# 2014_FDP_ACTIONNEUR.net
KiCad netlist of a schematic drawn in Altium Designer
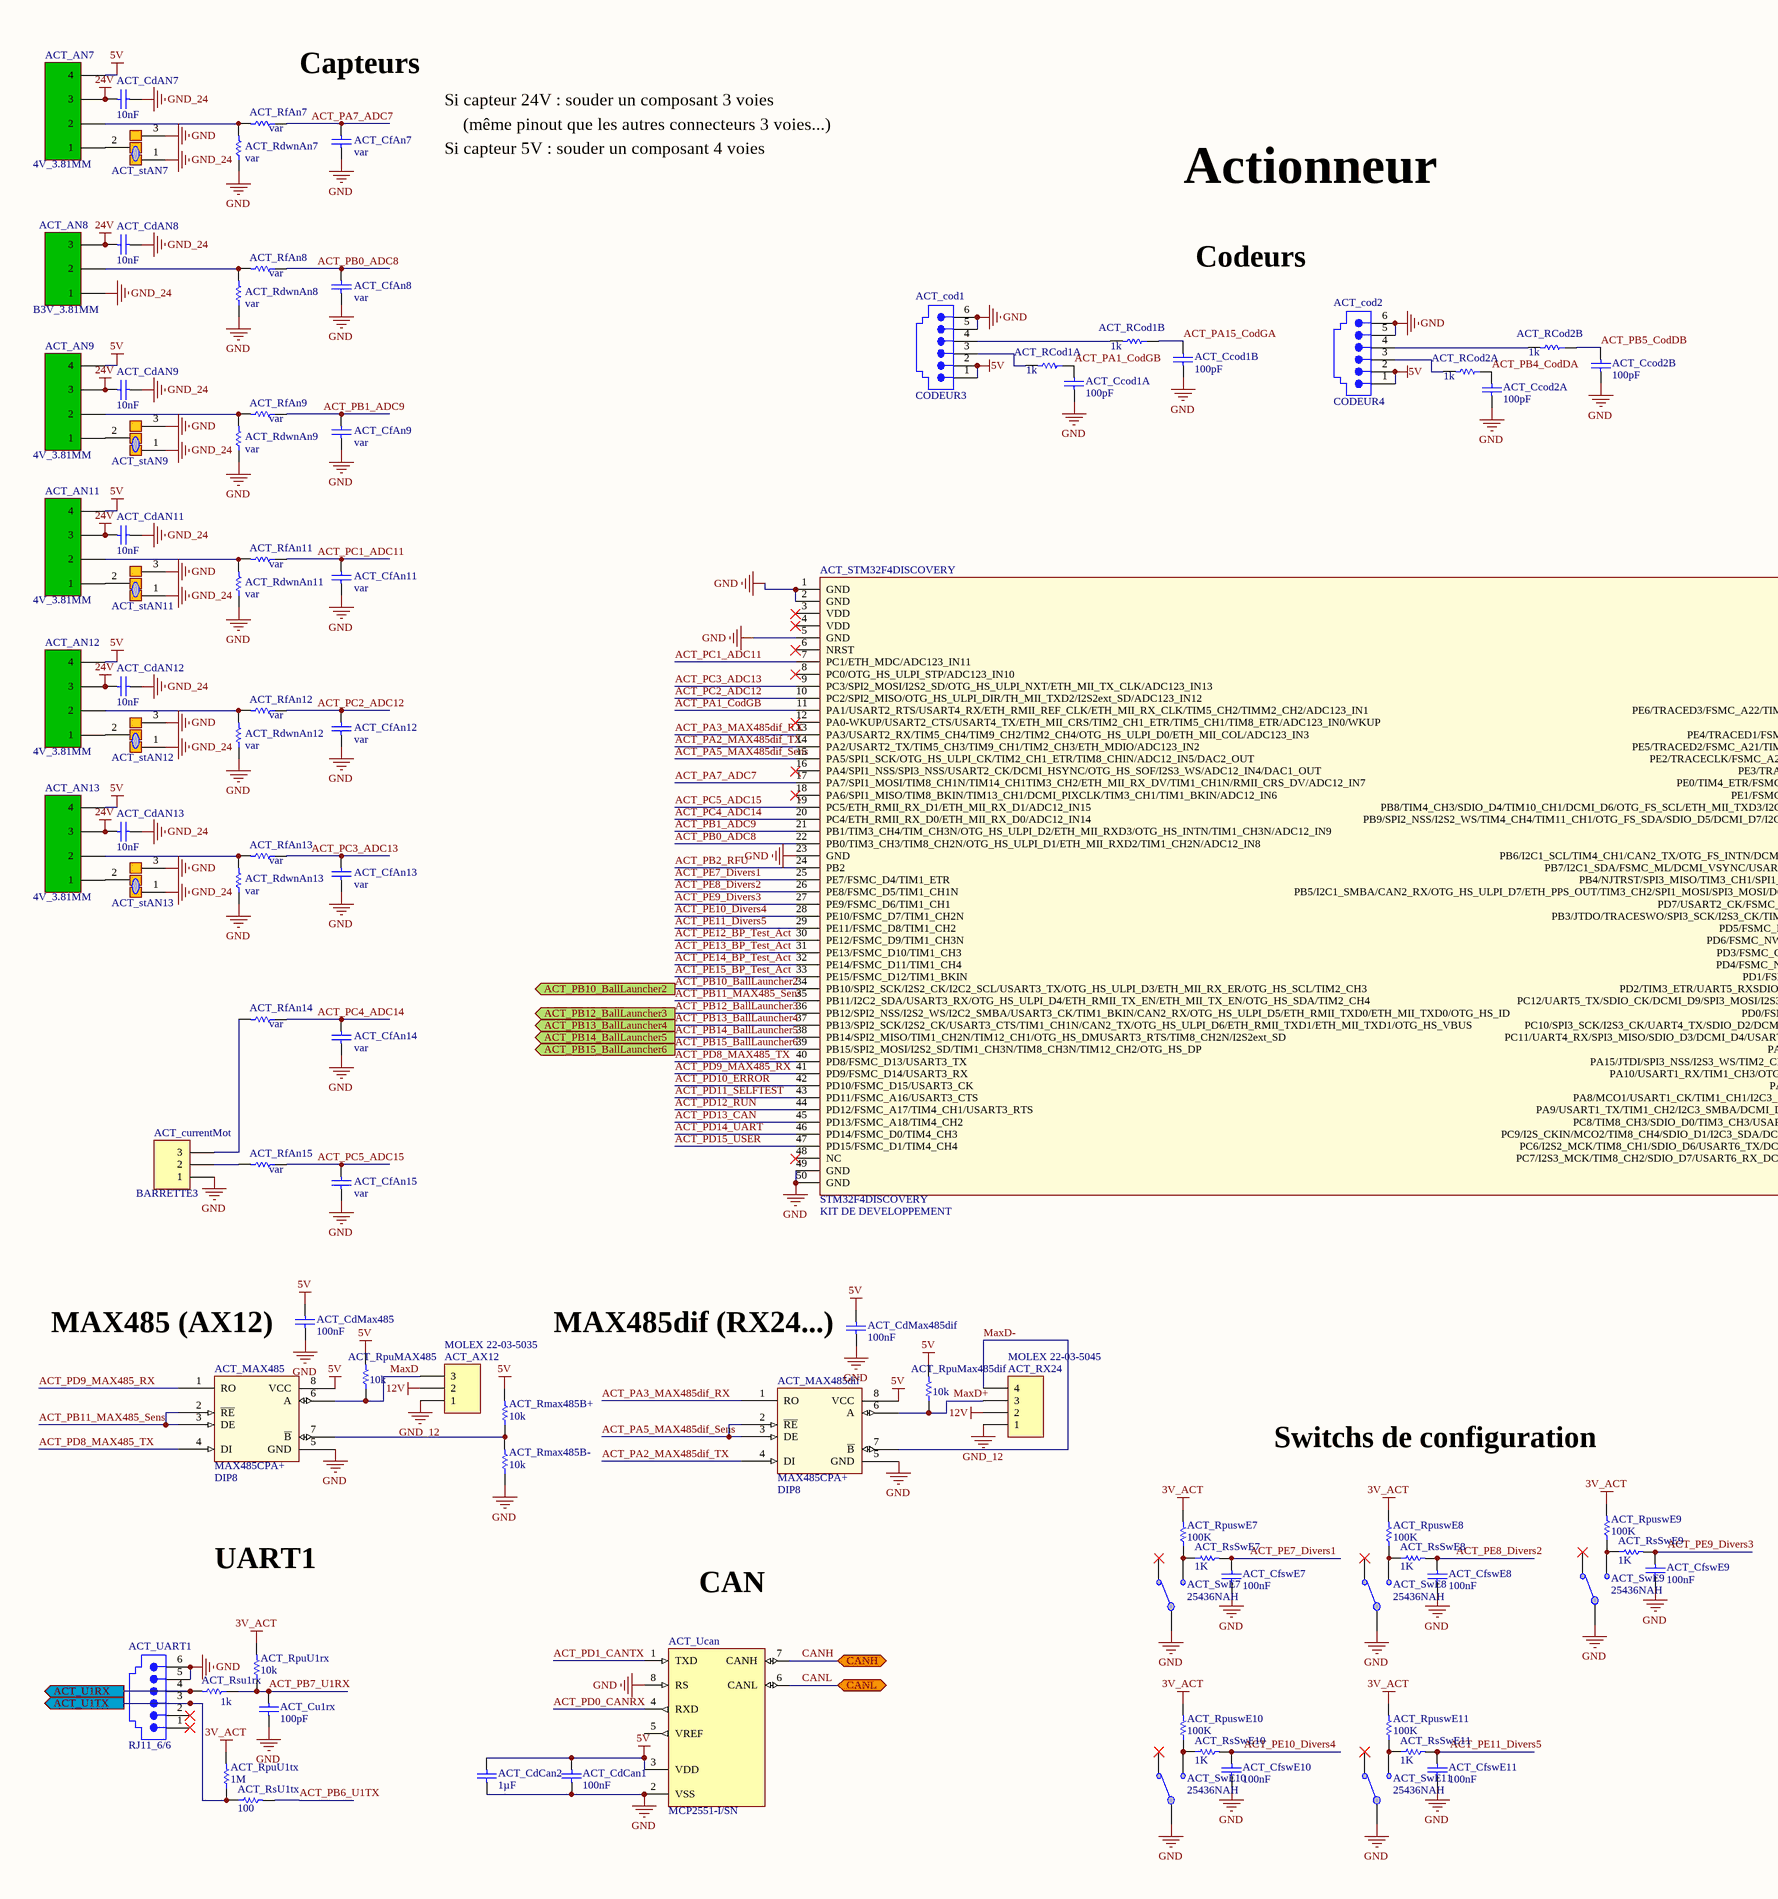
[diagram p0: 2014_FDP_ACTIONNEUR.SchDoc, left]
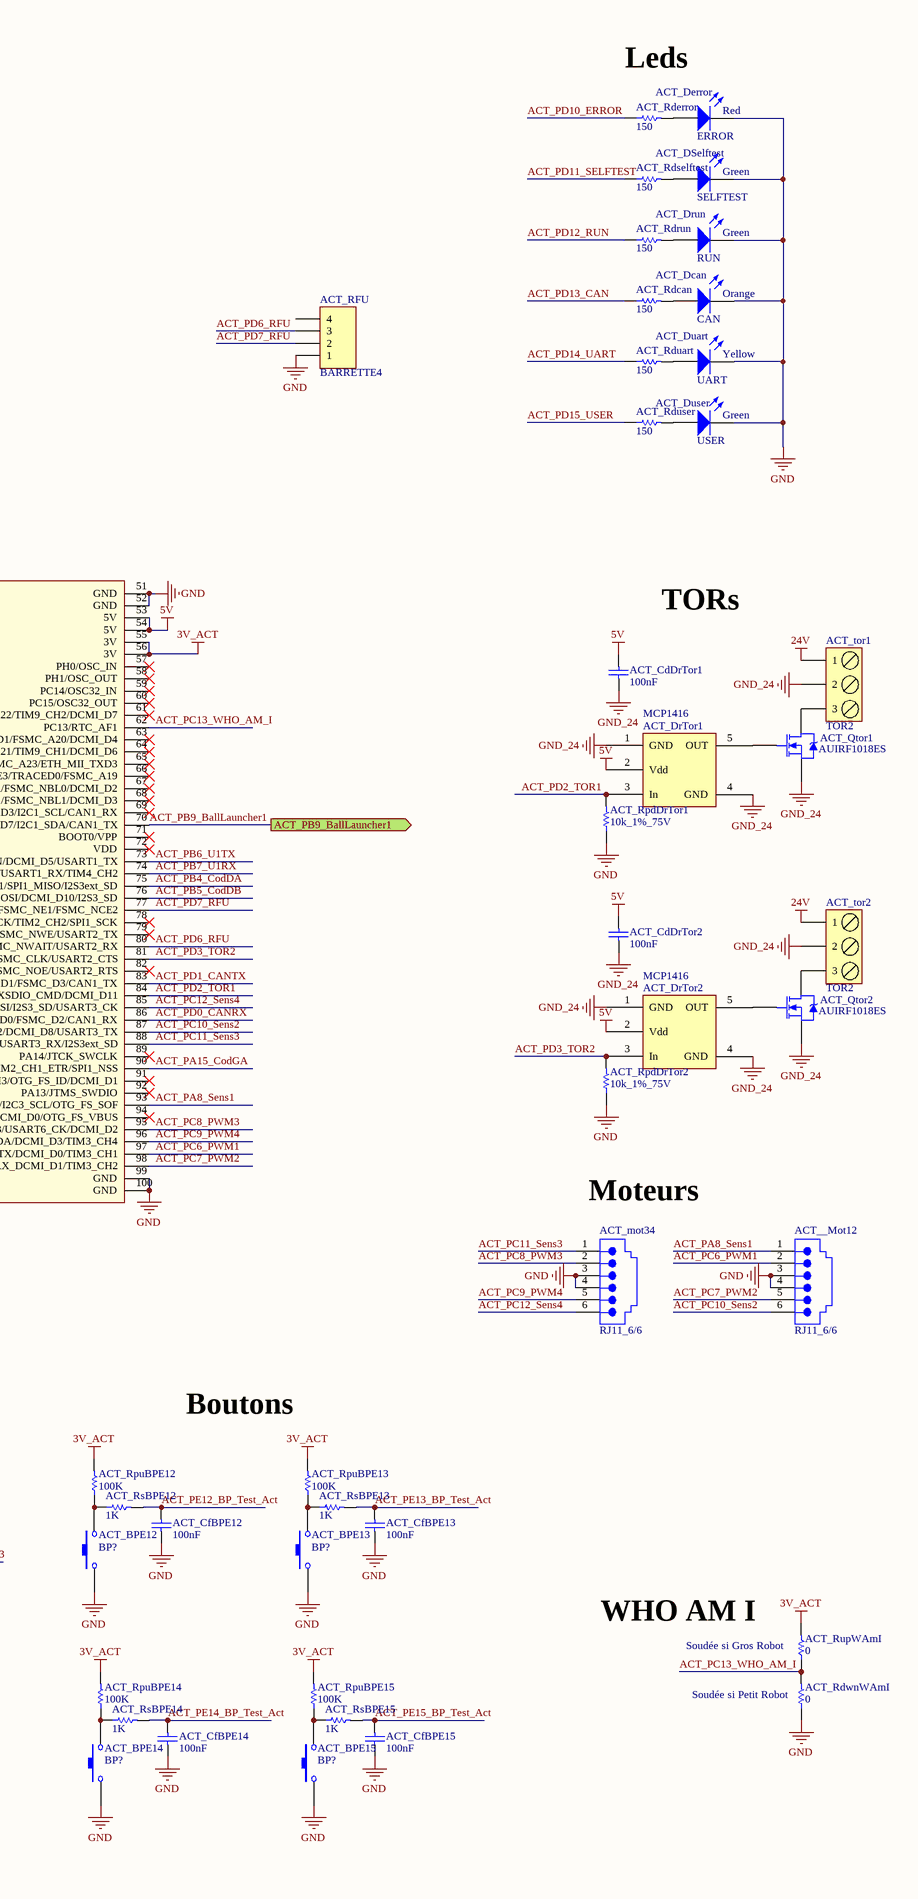
[diagram p1: 2014_FDP_ACTIONNEUR.SchDoc, right]

(export (version "E")
  (design (tool "Eeschema 10.0.6"))
  (components
    (comp (ref "ACT_AN7")
      (value "4V_3.81MM")
      (footprint "BORNIER_4V_3.81MM")
      (libsource (lib "Connecteur") (part "BORNIER_4V_3.81MM"))
    )
    (comp (ref "ACT_AN8")
      (value "B3V_3.81MM")
      (footprint "BORNIER_3V_3.81MM")
      (libsource (lib "Connecteur") (part "BORNIER_3V_3.81MM"))
    )
    (comp (ref "ACT_AN9")
      (value "4V_3.81MM")
      (footprint "BORNIER_4V_3.81MM")
      (libsource (lib "Connecteur") (part "BORNIER_4V_3.81MM"))
    )
    (comp (ref "ACT_AN11")
      (value "4V_3.81MM")
      (footprint "BORNIER_4V_3.81MM")
      (libsource (lib "Connecteur") (part "BORNIER_4V_3.81MM"))
    )
    (comp (ref "ACT_AN12")
      (value "4V_3.81MM")
      (footprint "BORNIER_4V_3.81MM")
      (libsource (lib "Connecteur") (part "BORNIER_4V_3.81MM"))
    )
    (comp (ref "ACT_AN13")
      (value "4V_3.81MM")
      (footprint "BORNIER_4V_3.81MM")
      (libsource (lib "Connecteur") (part "BORNIER_4V_3.81MM"))
    )
    (comp (ref "ACT_AX12")
      (value "MOLEX 22-03-5035")
      (footprint "MOLEX3_2.5MM")
      (description "Header, 3-Pin")
      (fields (field (name "PUBLISHER") "Altium Limited"))
      (libsource (lib "Connecteur") (part "BARRETTE3"))
    )
    (comp (ref "ACT_BPE12")
      (value "BP?")
      (footprint "Switch 6x6 Vertical")
      (description "Switch tactil 6mm x 6mm Vertical")
      (fields (field (name "PUBLISHER") "Damien Guitton"))
      (libsource (lib "_ROBOT") (part "SW_Pushbutton_6x6mm_Vertical"))
    )
    (comp (ref "ACT_BPE13")
      (value "BP?")
      (footprint "Switch 6x6 Vertical")
      (description "Switch tactil 6mm x 6mm Vertical")
      (fields (field (name "PUBLISHER") "Damien Guitton"))
      (libsource (lib "_ROBOT") (part "SW_Pushbutton_6x6mm_Vertical"))
    )
    (comp (ref "ACT_BPE14")
      (value "BP?")
      (footprint "Switch 6x6 Vertical")
      (description "Switch tactil 6mm x 6mm Vertical")
      (fields (field (name "PUBLISHER") "Damien Guitton"))
      (libsource (lib "_ROBOT") (part "SW_Pushbutton_6x6mm_Vertical"))
    )
    (comp (ref "ACT_BPE15")
      (value "BP?")
      (footprint "Switch 6x6 Vertical")
      (description "Switch tactil 6mm x 6mm Vertical")
      (fields (field (name "PUBLISHER") "Damien Guitton"))
      (libsource (lib "_ROBOT") (part "SW_Pushbutton_6x6mm_Vertical"))
    )
    (comp (ref "ACT_Ccod1A")
      (value "100pF")
      (footprint "C0805_N")
      (description "Capacitor")
      (fields (field (name "PUBLISHER") "Altium Limited"))
      (libsource (lib "_ROBOT") (part "Condensateur"))
    )
    (comp (ref "ACT_Ccod1B")
      (value "100pF")
      (footprint "C0805_N")
      (description "Capacitor")
      (fields (field (name "PUBLISHER") "Altium Limited"))
      (libsource (lib "_ROBOT") (part "Condensateur"))
    )
    (comp (ref "ACT_Ccod2A")
      (value "100pF")
      (footprint "C0805_N")
      (description "Capacitor")
      (fields (field (name "PUBLISHER") "Altium Limited"))
      (libsource (lib "_ROBOT") (part "Condensateur"))
    )
    (comp (ref "ACT_Ccod2B")
      (value "100pF")
      (footprint "C0805_N")
      (description "Capacitor")
      (fields (field (name "PUBLISHER") "Altium Limited"))
      (libsource (lib "_ROBOT") (part "Condensateur"))
    )
    (comp (ref "ACT_CdAN7")
      (value "10nF")
      (footprint "C0805_N")
      (description "Capacitor")
      (fields (field (name "PUBLISHER") "Altium Limited"))
      (libsource (lib "_ROBOT") (part "Condensateur"))
    )
    (comp (ref "ACT_CdAN8")
      (value "10nF")
      (footprint "C0805_N")
      (description "Capacitor")
      (fields (field (name "PUBLISHER") "Altium Limited"))
      (libsource (lib "_ROBOT") (part "Condensateur"))
    )
    (comp (ref "ACT_CdAN9")
      (value "10nF")
      (footprint "C0805_N")
      (description "Capacitor")
      (fields (field (name "PUBLISHER") "Altium Limited"))
      (libsource (lib "_ROBOT") (part "Condensateur"))
    )
    (comp (ref "ACT_CdAN11")
      (value "10nF")
      (footprint "C0805_N")
      (description "Capacitor")
      (fields (field (name "PUBLISHER") "Altium Limited"))
      (libsource (lib "_ROBOT") (part "Condensateur"))
    )
    (comp (ref "ACT_CdAN12")
      (value "10nF")
      (footprint "C0805_N")
      (description "Capacitor")
      (fields (field (name "PUBLISHER") "Altium Limited"))
      (libsource (lib "_ROBOT") (part "Condensateur"))
    )
    (comp (ref "ACT_CdAN13")
      (value "10nF")
      (footprint "C0805_N")
      (description "Capacitor")
      (fields (field (name "PUBLISHER") "Altium Limited"))
      (libsource (lib "_ROBOT") (part "Condensateur"))
    )
    (comp (ref "ACT_CdCan1")
      (value "100nF")
      (footprint "C0805_N")
      (description "Capacitor")
      (fields (field (name "PUBLISHER") "Altium Limited"))
      (libsource (lib "_ROBOT") (part "Condensateur"))
    )
    (comp (ref "ACT_CdCan2")
      (value "1µF")
      (footprint "C0805_N")
      (description "Capacitor")
      (fields (field (name "PUBLISHER") "Altium Limited"))
      (libsource (lib "_ROBOT") (part "Condensateur"))
    )
    (comp (ref "ACT_CdDrTor1")
      (value "100nF")
      (footprint "C0805_N")
      (description "Capacitor")
      (fields (field (name "PUBLISHER") "Altium Limited"))
      (libsource (lib "DG_Condensateur") (part "Capacitor"))
    )
    (comp (ref "ACT_CdDrTor2")
      (value "100nF")
      (footprint "C0805_N")
      (description "Capacitor")
      (fields (field (name "PUBLISHER") "Altium Limited"))
      (libsource (lib "DG_Condensateur") (part "Capacitor"))
    )
    (comp (ref "ACT_CdMax485")
      (value "100nF")
      (footprint "C0805_N")
      (description "Capacitor")
      (fields (field (name "PUBLISHER") "Altium Limited"))
      (libsource (lib "_ROBOT") (part "Condensateur"))
    )
    (comp (ref "ACT_CdMax485dif")
      (value "100nF")
      (footprint "C0805_N")
      (description "Capacitor")
      (fields (field (name "PUBLISHER") "Altium Limited"))
      (libsource (lib "_ROBOT") (part "Condensateur"))
    )
    (comp (ref "ACT_CfAn7")
      (value "var")
      (footprint "C0805_N")
      (description "Capacitor")
      (fields (field (name "PUBLISHER") "Altium Limited"))
      (libsource (lib "_ROBOT") (part "Condensateur"))
    )
    (comp (ref "ACT_CfAn8")
      (value "var")
      (footprint "C0805_N")
      (description "Capacitor")
      (fields (field (name "PUBLISHER") "Altium Limited"))
      (libsource (lib "_ROBOT") (part "Condensateur"))
    )
    (comp (ref "ACT_CfAn9")
      (value "var")
      (footprint "C0805_N")
      (description "Capacitor")
      (fields (field (name "PUBLISHER") "Altium Limited"))
      (libsource (lib "_ROBOT") (part "Condensateur"))
    )
    (comp (ref "ACT_CfAn11")
      (value "var")
      (footprint "C0805_N")
      (description "Capacitor")
      (fields (field (name "PUBLISHER") "Altium Limited"))
      (libsource (lib "_ROBOT") (part "Condensateur"))
    )
    (comp (ref "ACT_CfAn12")
      (value "var")
      (footprint "C0805_N")
      (description "Capacitor")
      (fields (field (name "PUBLISHER") "Altium Limited"))
      (libsource (lib "_ROBOT") (part "Condensateur"))
    )
    (comp (ref "ACT_CfAn13")
      (value "var")
      (footprint "C0805_N")
      (description "Capacitor")
      (fields (field (name "PUBLISHER") "Altium Limited"))
      (libsource (lib "_ROBOT") (part "Condensateur"))
    )
    (comp (ref "ACT_CfAn14")
      (value "var")
      (footprint "C0805_N")
      (description "Capacitor")
      (fields (field (name "PUBLISHER") "Altium Limited"))
      (libsource (lib "_ROBOT") (part "Condensateur"))
    )
    (comp (ref "ACT_CfAn15")
      (value "var")
      (footprint "C0805_N")
      (description "Capacitor")
      (fields (field (name "PUBLISHER") "Altium Limited"))
      (libsource (lib "_ROBOT") (part "Condensateur"))
    )
    (comp (ref "ACT_CfBPE12")
      (value "100nF")
      (footprint "C0805_N")
      (description "Capacitor")
      (fields (field (name "PUBLISHER") "Altium Limited"))
      (libsource (lib "_ROBOT") (part "Condensateur"))
    )
    (comp (ref "ACT_CfBPE13")
      (value "100nF")
      (footprint "C0805_N")
      (description "Capacitor")
      (fields (field (name "PUBLISHER") "Altium Limited"))
      (libsource (lib "_ROBOT") (part "Condensateur"))
    )
    (comp (ref "ACT_CfBPE14")
      (value "100nF")
      (footprint "C0805_N")
      (description "Capacitor")
      (fields (field (name "PUBLISHER") "Altium Limited"))
      (libsource (lib "_ROBOT") (part "Condensateur"))
    )
    (comp (ref "ACT_CfBPE15")
      (value "100nF")
      (footprint "C0805_N")
      (description "Capacitor")
      (fields (field (name "PUBLISHER") "Altium Limited"))
      (libsource (lib "_ROBOT") (part "Condensateur"))
    )
    (comp (ref "ACT_CfswE7")
      (value "100nF")
      (footprint "C0805_N")
      (description "Capacitor")
      (fields (field (name "PUBLISHER") "Altium Limited"))
      (libsource (lib "_ROBOT") (part "Condensateur"))
    )
    (comp (ref "ACT_CfswE8")
      (value "100nF")
      (footprint "C0805_N")
      (description "Capacitor")
      (fields (field (name "PUBLISHER") "Altium Limited"))
      (libsource (lib "_ROBOT") (part "Condensateur"))
    )
    (comp (ref "ACT_CfswE9")
      (value "100nF")
      (footprint "C0805_N")
      (description "Capacitor")
      (fields (field (name "PUBLISHER") "Altium Limited"))
      (libsource (lib "_ROBOT") (part "Condensateur"))
    )
    (comp (ref "ACT_CfswE10")
      (value "100nF")
      (footprint "C0805_N")
      (description "Capacitor")
      (fields (field (name "PUBLISHER") "Altium Limited"))
      (libsource (lib "_ROBOT") (part "Condensateur"))
    )
    (comp (ref "ACT_CfswE11")
      (value "100nF")
      (footprint "C0805_N")
      (description "Capacitor")
      (fields (field (name "PUBLISHER") "Altium Limited"))
      (libsource (lib "_ROBOT") (part "Condensateur"))
    )
    (comp (ref "ACT_cod1")
      (value "CODEUR3")
      (footprint "RJ11_6/6 - droit")
      (description "Right Angle, Standard Profile, Offset Latch DECconnect, Flangeless PCB Jack")
      (fields (field (name "PUBLISHER") "Altium Limited"))
      (libsource (lib "miniprojet") (part "RJ11_6/6"))
    )
    (comp (ref "ACT_cod2")
      (value "CODEUR4")
      (footprint "RJ11_6/6 - droit")
      (description "Right Angle, Standard Profile, Offset Latch DECconnect, Flangeless PCB Jack")
      (fields (field (name "PUBLISHER") "Altium Limited"))
      (libsource (lib "miniprojet") (part "RJ11_6/6"))
    )
    (comp (ref "ACT_Cu1rx")
      (value "100pF")
      (footprint "C0805_N")
      (description "Capacitor")
      (fields (field (name "PUBLISHER") "Altium Limited"))
      (libsource (lib "_ROBOT") (part "Condensateur"))
    )
    (comp (ref "ACT_currentMot")
      (value "BARRETTE3")
      (footprint "HE14_3")
      (description "Header, 3-Pin")
      (fields (field (name "PUBLISHER") "Altium Limited"))
      (libsource (lib "") (part "BARRETTE3_1"))
    )
    (comp (ref "ACT_Dcan")
      (value "CAN")
      (footprint "LED_0805")
      (description "Typical LED")
      (fields (field (name "PUBLISHER") "Altium Limited"))
      (libsource (lib "_ROBOT") (part "LED"))
    )
    (comp (ref "ACT_Derror")
      (value "ERROR")
      (footprint "LED_0805")
      (description "Typical LED")
      (fields (field (name "PUBLISHER") "Altium Limited"))
      (libsource (lib "_ROBOT") (part "LED"))
    )
    (comp (ref "ACT_DrTor1")
      (value "MCP1416")
      (footprint "SOT23-5AN")
      (libsource (lib "GAL") (part "MCP1402"))
    )
    (comp (ref "ACT_DrTor2")
      (value "MCP1416")
      (footprint "SOT23-5AN")
      (libsource (lib "GAL") (part "MCP1402"))
    )
    (comp (ref "ACT_Drun")
      (value "RUN")
      (footprint "LED_0805")
      (description "Typical LED")
      (fields (field (name "PUBLISHER") "Altium Limited"))
      (libsource (lib "_ROBOT") (part "LED"))
    )
    (comp (ref "ACT_DSelftest")
      (value "SELFTEST")
      (footprint "LED_0805")
      (description "Typical LED")
      (fields (field (name "PUBLISHER") "Altium Limited"))
      (libsource (lib "_ROBOT") (part "LED"))
    )
    (comp (ref "ACT_Duart")
      (value "UART")
      (footprint "LED_0805")
      (description "Typical LED")
      (fields (field (name "PUBLISHER") "Altium Limited"))
      (libsource (lib "_ROBOT") (part "LED"))
    )
    (comp (ref "ACT_Duser")
      (value "USER")
      (footprint "LED_0805")
      (description "Typical LED")
      (fields (field (name "PUBLISHER") "Altium Limited"))
      (libsource (lib "_ROBOT") (part "LED"))
    )
    (comp (ref "ACT_MAX485")
      (value "MAX485CPA+_DIP8")
      (footprint "SO8_N")
      (description "EMETTEUR/RECEPTEUR FAIBLE PUISSANCE DE LIAISONS RS422/RS485 - DIP8")
      (fields (field (name "TYPE") "MAX485CPA+") (field (name "PACKAGE") "DIP8"))
      (libsource (lib "circuits integres") (part "MAX485CPA+_DIP8"))
    )
    (comp (ref "ACT_MAX485dif")
      (value "MAX485CPA+_DIP8")
      (footprint "SO8_N")
      (description "EMETTEUR/RECEPTEUR FAIBLE PUISSANCE DE LIAISONS RS422/RS485 - DIP8")
      (fields (field (name "TYPE") "MAX485CPA+") (field (name "PACKAGE") "DIP8"))
      (libsource (lib "circuits integres") (part "MAX485CPA+_DIP8"))
    )
    (comp (ref "ACT_mot34")
      (value "RJ11_6/6")
      (footprint "RJ11_6/6")
      (description "Right Angle, Standard Profile, Offset Latch DECconnect, Flangeless PCB Jack")
      (fields (field (name "PUBLISHER") "Altium Limited"))
      (libsource (lib "Connecteur") (part "RJ11_6/6"))
    )
    (comp (ref "ACT_Qtor1")
      (value "AUIRF1018ES")
      (footprint "D2PAK")
      (description "HEXFET N-Channel Power MOSFET")
      (fields (field (name "PUBLISHER") "Altium Limited"))
      (libsource (lib "IR Discrete MOSFET - Power") (part "IRF1010S"))
    )
    (comp (ref "ACT_Qtor2")
      (value "AUIRF1018ES")
      (footprint "D2PAK")
      (description "HEXFET N-Channel Power MOSFET")
      (fields (field (name "PUBLISHER") "Altium Limited"))
      (libsource (lib "IR Discrete MOSFET - Power") (part "IRF1010S"))
    )
    (comp (ref "ACT_RCod1A")
      (value "1k")
      (footprint "R1206_N")
      (description "Resistor")
      (fields (field (name "PUBLISHER") "Altium Limited"))
      (libsource (lib "_ROBOT") (part "Resistor"))
    )
    (comp (ref "ACT_RCod1B")
      (value "1k")
      (footprint "R1206_N")
      (description "Resistor")
      (fields (field (name "PUBLISHER") "Altium Limited"))
      (libsource (lib "_ROBOT") (part "Resistor"))
    )
    (comp (ref "ACT_RCod2A")
      (value "1k")
      (footprint "R1206_N")
      (description "Resistor")
      (fields (field (name "PUBLISHER") "Altium Limited"))
      (libsource (lib "_ROBOT") (part "Resistor"))
    )
    (comp (ref "ACT_RCod2B")
      (value "1k")
      (footprint "R1206_N")
      (description "Resistor")
      (fields (field (name "PUBLISHER") "Altium Limited"))
      (libsource (lib "_ROBOT") (part "Resistor"))
    )
    (comp (ref "ACT_Rdcan")
      (value "150")
      (footprint "R1206_N")
      (description "Resistor")
      (fields (field (name "PUBLISHER") "Altium Limited"))
      (libsource (lib "_ROBOT") (part "Resistor"))
    )
    (comp (ref "ACT_Rderror")
      (value "150")
      (footprint "R1206_N")
      (description "Resistor")
      (fields (field (name "PUBLISHER") "Altium Limited"))
      (libsource (lib "_ROBOT") (part "Resistor"))
    )
    (comp (ref "ACT_Rdrun")
      (value "150")
      (footprint "R1206_N")
      (description "Resistor")
      (fields (field (name "PUBLISHER") "Altium Limited"))
      (libsource (lib "_ROBOT") (part "Resistor"))
    )
    (comp (ref "ACT_Rdselftest")
      (value "150")
      (footprint "R1206_N")
      (description "Resistor")
      (fields (field (name "PUBLISHER") "Altium Limited"))
      (libsource (lib "_ROBOT") (part "Resistor"))
    )
    (comp (ref "ACT_Rduart")
      (value "150")
      (footprint "R1206_N")
      (description "Resistor")
      (fields (field (name "PUBLISHER") "Altium Limited"))
      (libsource (lib "_ROBOT") (part "Resistor"))
    )
    (comp (ref "ACT_Rduser")
      (value "150")
      (footprint "R1206_N")
      (description "Resistor")
      (fields (field (name "PUBLISHER") "Altium Limited"))
      (libsource (lib "_ROBOT") (part "Resistor"))
    )
    (comp (ref "ACT_RdwnAn7")
      (value "var")
      (footprint "R1206_N")
      (description "Resistor")
      (fields (field (name "PUBLISHER") "Altium Limited"))
      (libsource (lib "_ROBOT") (part "Resistor"))
    )
    (comp (ref "ACT_RdwnAn8")
      (value "var")
      (footprint "R1206_N")
      (description "Resistor")
      (fields (field (name "PUBLISHER") "Altium Limited"))
      (libsource (lib "_ROBOT") (part "Resistor"))
    )
    (comp (ref "ACT_RdwnAn9")
      (value "var")
      (footprint "R1206_N")
      (description "Resistor")
      (fields (field (name "PUBLISHER") "Altium Limited"))
      (libsource (lib "_ROBOT") (part "Resistor"))
    )
    (comp (ref "ACT_RdwnAn11")
      (value "var")
      (footprint "R1206_N")
      (description "Resistor")
      (fields (field (name "PUBLISHER") "Altium Limited"))
      (libsource (lib "_ROBOT") (part "Resistor"))
    )
    (comp (ref "ACT_RdwnAn12")
      (value "var")
      (footprint "R1206_N")
      (description "Resistor")
      (fields (field (name "PUBLISHER") "Altium Limited"))
      (libsource (lib "_ROBOT") (part "Resistor"))
    )
    (comp (ref "ACT_RdwnAn13")
      (value "var")
      (footprint "R1206_N")
      (description "Resistor")
      (fields (field (name "PUBLISHER") "Altium Limited"))
      (libsource (lib "_ROBOT") (part "Resistor"))
    )
    (comp (ref "ACT_RdwnWAmI")
      (value "0")
      (footprint "R1206_N")
      (description "Resistor")
      (fields (field (name "PUBLISHER") "Altium Limited"))
      (libsource (lib "_ROBOT") (part "Resistor"))
    )
    (comp (ref "ACT_RfAn7")
      (value "var")
      (footprint "R1206_N")
      (description "Resistor")
      (fields (field (name "PUBLISHER") "Altium Limited"))
      (libsource (lib "_ROBOT") (part "Resistor"))
    )
    (comp (ref "ACT_RfAn8")
      (value "var")
      (footprint "R1206_N")
      (description "Resistor")
      (fields (field (name "PUBLISHER") "Altium Limited"))
      (libsource (lib "_ROBOT") (part "Resistor"))
    )
    (comp (ref "ACT_RfAn9")
      (value "var")
      (footprint "R1206_N")
      (description "Resistor")
      (fields (field (name "PUBLISHER") "Altium Limited"))
      (libsource (lib "_ROBOT") (part "Resistor"))
    )
    (comp (ref "ACT_RfAn11")
      (value "var")
      (footprint "R1206_N")
      (description "Resistor")
      (fields (field (name "PUBLISHER") "Altium Limited"))
      (libsource (lib "_ROBOT") (part "Resistor"))
    )
    (comp (ref "ACT_RfAn12")
      (value "var")
      (footprint "R1206_N")
      (description "Resistor")
      (fields (field (name "PUBLISHER") "Altium Limited"))
      (libsource (lib "_ROBOT") (part "Resistor"))
    )
    (comp (ref "ACT_RfAn13")
      (value "var")
      (footprint "R1206_N")
      (description "Resistor")
      (fields (field (name "PUBLISHER") "Altium Limited"))
      (libsource (lib "_ROBOT") (part "Resistor"))
    )
    (comp (ref "ACT_RfAn14")
      (value "var")
      (footprint "R1206_N")
      (description "Resistor")
      (fields (field (name "PUBLISHER") "Altium Limited"))
      (libsource (lib "_ROBOT") (part "Resistor"))
    )
    (comp (ref "ACT_RfAn15")
      (value "var")
      (footprint "R1206_N")
      (description "Resistor")
      (fields (field (name "PUBLISHER") "Altium Limited"))
      (libsource (lib "_ROBOT") (part "Resistor"))
    )
    (comp (ref "ACT_RFU")
      (value "BARRETTE4")
      (footprint "HE14_4")
      (description "Header, 4-Pin")
      (fields (field (name "PUBLISHER") "Altium Limited"))
      (libsource (lib "Connecteur") (part "BARRETTE4"))
    )
    (comp (ref "ACT_Rmax485B+")
      (value "10k")
      (footprint "R1206_N")
      (description "Resistor")
      (fields (field (name "PUBLISHER") "Altium Limited"))
      (libsource (lib "_ROBOT") (part "Resistor"))
    )
    (comp (ref "ACT_Rmax485B-")
      (value "10k")
      (footprint "R1206_N")
      (description "Resistor")
      (fields (field (name "PUBLISHER") "Altium Limited"))
      (libsource (lib "_ROBOT") (part "Resistor"))
    )
    (comp (ref "ACT_RpdDrTor1")
      (value "10k_1%_75V")
      (footprint "R1206_N")
      (description "Resistor")
      (fields (field (name "PUBLISHER") "Altium Limited"))
      (libsource (lib "DG_Resistance") (part "Resistor"))
    )
    (comp (ref "ACT_RpdDrTor2")
      (value "10k_1%_75V")
      (footprint "R1206_N")
      (description "Resistor")
      (fields (field (name "PUBLISHER") "Altium Limited"))
      (libsource (lib "DG_Resistance") (part "Resistor"))
    )
    (comp (ref "ACT_RpuBPE12")
      (value "100K")
      (footprint "R1206_N")
      (description "Resistor")
      (fields (field (name "PUBLISHER") "Altium Limited"))
      (libsource (lib "_ROBOT") (part "Resistor"))
    )
    (comp (ref "ACT_RpuBPE13")
      (value "100K")
      (footprint "R1206_N")
      (description "Resistor")
      (fields (field (name "PUBLISHER") "Altium Limited"))
      (libsource (lib "_ROBOT") (part "Resistor"))
    )
    (comp (ref "ACT_RpuBPE14")
      (value "100K")
      (footprint "R1206_N")
      (description "Resistor")
      (fields (field (name "PUBLISHER") "Altium Limited"))
      (libsource (lib "_ROBOT") (part "Resistor"))
    )
    (comp (ref "ACT_RpuBPE15")
      (value "100K")
      (footprint "R1206_N")
      (description "Resistor")
      (fields (field (name "PUBLISHER") "Altium Limited"))
      (libsource (lib "_ROBOT") (part "Resistor"))
    )
    (comp (ref "ACT_RpuMAX485")
      (value "10k")
      (footprint "R1206_N")
      (description "Resistor")
      (fields (field (name "PUBLISHER") "Altium Limited"))
      (libsource (lib "_ROBOT") (part "Resistor"))
    )
    (comp (ref "ACT_RpuMax485dif")
      (value "10k")
      (footprint "R1206_N")
      (description "Resistor")
      (fields (field (name "PUBLISHER") "Altium Limited"))
      (libsource (lib "_ROBOT") (part "Resistor"))
    )
    (comp (ref "ACT_RpuswE7")
      (value "100K")
      (footprint "R1206_N")
      (description "Resistor")
      (fields (field (name "PUBLISHER") "Altium Limited"))
      (libsource (lib "_ROBOT") (part "Resistor"))
    )
    (comp (ref "ACT_RpuswE8")
      (value "100K")
      (footprint "R1206_N")
      (description "Resistor")
      (fields (field (name "PUBLISHER") "Altium Limited"))
      (libsource (lib "_ROBOT") (part "Resistor"))
    )
    (comp (ref "ACT_RpuswE9")
      (value "100K")
      (footprint "R1206_N")
      (description "Resistor")
      (fields (field (name "PUBLISHER") "Altium Limited"))
      (libsource (lib "_ROBOT") (part "Resistor"))
    )
    (comp (ref "ACT_RpuswE10")
      (value "100K")
      (footprint "R1206_N")
      (description "Resistor")
      (fields (field (name "PUBLISHER") "Altium Limited"))
      (libsource (lib "_ROBOT") (part "Resistor"))
    )
    (comp (ref "ACT_RpuswE11")
      (value "100K")
      (footprint "R1206_N")
      (description "Resistor")
      (fields (field (name "PUBLISHER") "Altium Limited"))
      (libsource (lib "_ROBOT") (part "Resistor"))
    )
    (comp (ref "ACT_RpuU1rx")
      (value "10k")
      (footprint "R1206_N")
      (description "Resistor")
      (fields (field (name "PUBLISHER") "Altium Limited"))
      (libsource (lib "_ROBOT") (part "Resistor"))
    )
    (comp (ref "ACT_RpuU1tx")
      (value "1M")
      (footprint "R1206_N")
      (description "Resistor")
      (fields (field (name "PUBLISHER") "Altium Limited"))
      (libsource (lib "_ROBOT") (part "Resistor"))
    )
    (comp (ref "ACT_RsBPE12")
      (value "1K")
      (footprint "R1206_N")
      (description "Resistor")
      (fields (field (name "PUBLISHER") "Altium Limited"))
      (libsource (lib "_ROBOT") (part "Resistor"))
    )
    (comp (ref "ACT_RsBPE13")
      (value "1K")
      (footprint "R1206_N")
      (description "Resistor")
      (fields (field (name "PUBLISHER") "Altium Limited"))
      (libsource (lib "_ROBOT") (part "Resistor"))
    )
    (comp (ref "ACT_RsBPE14")
      (value "1K")
      (footprint "R1206_N")
      (description "Resistor")
      (fields (field (name "PUBLISHER") "Altium Limited"))
      (libsource (lib "_ROBOT") (part "Resistor"))
    )
    (comp (ref "ACT_RsBPE15")
      (value "1K")
      (footprint "R1206_N")
      (description "Resistor")
      (fields (field (name "PUBLISHER") "Altium Limited"))
      (libsource (lib "_ROBOT") (part "Resistor"))
    )
    (comp (ref "ACT_RsSwE7")
      (value "1K")
      (footprint "R1206_N")
      (description "Resistor")
      (fields (field (name "PUBLISHER") "Altium Limited"))
      (libsource (lib "_ROBOT") (part "Resistor"))
    )
    (comp (ref "ACT_RsSwE8")
      (value "1K")
      (footprint "R1206_N")
      (description "Resistor")
      (fields (field (name "PUBLISHER") "Altium Limited"))
      (libsource (lib "_ROBOT") (part "Resistor"))
    )
    (comp (ref "ACT_RsSwE9")
      (value "1K")
      (footprint "R1206_N")
      (description "Resistor")
      (fields (field (name "PUBLISHER") "Altium Limited"))
      (libsource (lib "_ROBOT") (part "Resistor"))
    )
    (comp (ref "ACT_RsSwE10")
      (value "1K")
      (footprint "R1206_N")
      (description "Resistor")
      (fields (field (name "PUBLISHER") "Altium Limited"))
      (libsource (lib "_ROBOT") (part "Resistor"))
    )
    (comp (ref "ACT_RsSwE11")
      (value "1K")
      (footprint "R1206_N")
      (description "Resistor")
      (fields (field (name "PUBLISHER") "Altium Limited"))
      (libsource (lib "_ROBOT") (part "Resistor"))
    )
    (comp (ref "ACT_Rsu1rx")
      (value "1k")
      (footprint "R1206_N")
      (description "Resistor")
      (fields (field (name "PUBLISHER") "Altium Limited"))
      (libsource (lib "_ROBOT") (part "Resistor"))
    )
    (comp (ref "ACT_RsU1tx")
      (value "100")
      (footprint "R1206_N")
      (description "Resistor")
      (fields (field (name "PUBLISHER") "Altium Limited"))
      (libsource (lib "_ROBOT") (part "Resistor"))
    )
    (comp (ref "ACT_RupWAmI")
      (value "0")
      (footprint "R1206_N")
      (description "Resistor")
      (fields (field (name "PUBLISHER") "Altium Limited"))
      (libsource (lib "_ROBOT") (part "Resistor"))
    )
    (comp (ref "ACT_RX24")
      (value "MOLEX 22-03-5045")
      (footprint "MOLEX4_2.5MM")
      (description "Header, 4-Pin")
      (fields (field (name "PUBLISHER") "Altium Limited"))
      (libsource (lib "Connecteur") (part "BARRETTE4"))
    )
    (comp (ref "ACT_stAN7")
      (value "strap")
      (footprint "Goutte Strap_3")
      (description "Goutte Strap_3")
      (fields (field (name "PUBLISHER") "Damien Guitton"))
      (libsource (lib "DG_Connecteur") (part "Goutte Strap_3"))
    )
    (comp (ref "ACT_stAN9")
      (value "strap")
      (footprint "Goutte Strap_3")
      (description "Goutte Strap_3")
      (fields (field (name "PUBLISHER") "Damien Guitton"))
      (libsource (lib "DG_Connecteur") (part "Goutte Strap_3"))
    )
    (comp (ref "ACT_stAN11")
      (value "strap")
      (footprint "Goutte Strap_3")
      (description "Goutte Strap_3")
      (fields (field (name "PUBLISHER") "Damien Guitton"))
      (libsource (lib "DG_Connecteur") (part "Goutte Strap_3"))
    )
    (comp (ref "ACT_stAN12")
      (value "strap")
      (footprint "Goutte Strap_3")
      (description "Goutte Strap_3")
      (fields (field (name "PUBLISHER") "Damien Guitton"))
      (libsource (lib "DG_Connecteur") (part "Goutte Strap_3"))
    )
    (comp (ref "ACT_stAN13")
      (value "strap")
      (footprint "Goutte Strap_3")
      (description "Goutte Strap_3")
      (fields (field (name "PUBLISHER") "Damien Guitton"))
      (libsource (lib "DG_Connecteur") (part "Goutte Strap_3"))
    )
    (comp (ref "ACT_STM32F4DISCOVERY")
      (value "STM32F4DISCOVERY")
      (footprint "STM32_F4DISCOVERY")
      (description "KIT DE DEVELOPPEMENT POUR MICROCONTROLEUR STM32F407VGT6")
      (fields (field (name "TYPE") "KIT DE DEVELOPPEMENT"))
      (libsource (lib "circuits integres") (part "STM32F4DISCOVERY"))
    )
    (comp (ref "ACT_SwE7")
      (value "25436NAH")
      (footprint "SW_UNIPOL_DROIT - APEM 18235")
      (description "Switch unipolaire a levier")
      (libsource (lib "_ROBOT") (part "SW SPDT- APEM Série 523x"))
    )
    (comp (ref "ACT_SwE8")
      (value "25436NAH")
      (footprint "SW_UNIPOL_DROIT - APEM 18235")
      (description "Switch unipolaire a levier")
      (libsource (lib "_ROBOT") (part "SW SPDT- APEM Série 523x"))
    )
    (comp (ref "ACT_SwE9")
      (value "25436NAH")
      (footprint "SW_UNIPOL_DROIT - APEM 18235")
      (description "Switch unipolaire a levier")
      (libsource (lib "_ROBOT") (part "SW SPDT- APEM Série 523x"))
    )
    (comp (ref "ACT_SwE10")
      (value "25436NAH")
      (footprint "SW_UNIPOL_DROIT - APEM 18235")
      (description "Switch unipolaire a levier")
      (libsource (lib "_ROBOT") (part "SW SPDT- APEM Série 523x"))
    )
    (comp (ref "ACT_SwE11")
      (value "25436NAH")
      (footprint "SW_UNIPOL_DROIT - APEM 18235")
      (description "Switch unipolaire a levier")
      (libsource (lib "_ROBOT") (part "SW SPDT- APEM Série 523x"))
    )
    (comp (ref "ACT_tor1")
      (value "TOR2")
      (footprint "BORNIER3_FEM_COUDE")
      (description "Terminal blocks, 2 pins, pitch=5mm")
      (libsource (lib "miniprojet") (part "BORNIER3"))
    )
    (comp (ref "ACT_tor2")
      (value "TOR2")
      (footprint "BORNIER3_FEM_COUDE")
      (description "Terminal blocks, 2 pins, pitch=5mm")
      (libsource (lib "miniprojet") (part "BORNIER3"))
    )
    (comp (ref "ACT_UART1")
      (value "RJ11_6/6")
      (footprint "RJ11_6/6")
      (description "Right Angle, Standard Profile, Offset Latch DECconnect, Flangeless PCB Jack")
      (fields (field (name "PUBLISHER") "Altium Limited"))
      (libsource (lib "Connecteur") (part "RJ11_6/6"))
    )
    (comp (ref "ACT_Ucan")
      (value "MCP2551-I/SN")
      (footprint "SO8_N")
      (description "High-Speed CAN Transceiver, 8-Pin SOIC, Industrial Temperature")
      (fields (field (name "PUBLISHER") "Damien Guitton"))
      (libsource (lib "Circuit intégré") (part "MCP2551-I/SN"))
    )
    (comp (ref "ACT__Mot12")
      (value "RJ11_6/6")
      (footprint "RJ11_6/6")
      (description "Right Angle, Standard Profile, Offset Latch DECconnect, Flangeless PCB Jack")
      (fields (field (name "PUBLISHER") "Altium Limited"))
      (libsource (lib "Connecteur") (part "RJ11_6/6"))
    )
  )
  (nets
    (net (code "1") (name "/ACT_PA1_CodGB") (class "Default")
      (node (ref "ACT_Ccod1A") (pin "2") (pinfunction "2_2") (pintype "passive"))
      (node (ref "ACT_RCod1A") (pin "1") (pinfunction "1_1") (pintype "passive"))
      (node (ref "ACT_STM32F4DISCOVERY") (pin "11") (pinfunction "PA1/USART2_RTS/USART4_RX/ETH_RMII_REF_CLK/ETH_MII_RX_CLK/TIM5_CH2/TIMM2_CH2/ADC123_IN1_11") (pintype "passive"))
    )
    (net (code "2") (name "/ACT_PA2_MAX485dif_TX") (class "Default")
      (node (ref "ACT_MAX485dif") (pin "4") (pinfunction "DI_4") (pintype "input"))
      (node (ref "ACT_STM32F4DISCOVERY") (pin "14") (pinfunction "PA2/USART2_TX/TIM5_CH3/TIM9_CH1/TIM2_CH3/ETH_MDIO/ADC123_IN2_14") (pintype "passive"))
    )
    (net (code "3") (name "/ACT_PA3_MAX485dif_RX") (class "Default")
      (node (ref "ACT_MAX485dif") (pin "1") (pinfunction "RO_1") (pintype "tri_state"))
      (node (ref "ACT_STM32F4DISCOVERY") (pin "13") (pinfunction "PA3/USART2_RX/TIM5_CH4/TIM9_CH2/TIM2_CH4/OTG_HS_ULPI_D0/ETH_MII_COL/ADC123_IN3_13") (pintype "passive"))
    )
    (net (code "4") (name "/ACT_PA5_MAX485dif_Sens") (class "Default")
      (node (ref "ACT_MAX485dif") (pin "2") (pinfunction "~{RE}_2") (pintype "input"))
      (node (ref "ACT_MAX485dif") (pin "3") (pinfunction "DE_3") (pintype "input"))
      (node (ref "ACT_STM32F4DISCOVERY") (pin "15") (pinfunction "PA5/SPI1_SCK/OTG_HS_ULPI_CK/TIM2_CH1_ETR/TIM8_CHIN/ADC12_IN5/DAC2_OUT_15") (pintype "passive"))
    )
    (net (code "5") (name "/ACT_PA7_ADC7") (class "Default")
      (node (ref "ACT_CfAn7") (pin "2") (pinfunction "2_2") (pintype "passive"))
      (node (ref "ACT_RfAn7") (pin "1") (pinfunction "1_1") (pintype "passive"))
      (node (ref "ACT_STM32F4DISCOVERY") (pin "17") (pinfunction "PA7/SPI1_MOSI/TIM8_CH1N/TIM14_CH1TIM3_CH2/ETH_MII_RX_DV/TIM1_CH1N/RMII_CRS_DV/ADC12_IN7_17") (pintype "passive"))
    )
    (net (code "6") (name "/ACT_PA8_Sens1") (class "Default")
      (node (ref "ACT_STM32F4DISCOVERY") (pin "93") (pinfunction "PA8/MCO1/USART1_CK/TIM1_CH1/I2C3_SCL/OTG_FS_SOF_93") (pintype "passive"))
      (node (ref "ACT__Mot12") (pin "1") (pinfunction "1_1") (pintype "passive"))
    )
    (net (code "7") (name "/ACT_PA15_CodGA") (class "Default")
      (node (ref "ACT_Ccod1B") (pin "2") (pinfunction "2_2") (pintype "passive"))
      (node (ref "ACT_RCod1B") (pin "1") (pinfunction "1_1") (pintype "passive"))
      (node (ref "ACT_STM32F4DISCOVERY") (pin "90") (pinfunction "PA15/JTDI/SPI3_NSS/I2S3_WS/TIM2_CH1_ETR/SPI1_NSS_90") (pintype "passive"))
    )
    (net (code "8") (name "/ACT_PB0_ADC8") (class "Default")
      (node (ref "ACT_CfAn8") (pin "2") (pinfunction "2_2") (pintype "passive"))
      (node (ref "ACT_RfAn8") (pin "1") (pinfunction "1_1") (pintype "passive"))
      (node (ref "ACT_STM32F4DISCOVERY") (pin "22") (pinfunction "PB0/TIM3_CH3/TIM8_CH2N/OTG_HS_ULPI_D1/ETH_MII_RXD2/TIM1_CH2N/ADC12_IN8_22") (pintype "passive"))
    )
    (net (code "9") (name "/ACT_PB1_ADC9") (class "Default")
      (node (ref "ACT_CfAn9") (pin "2") (pinfunction "2_2") (pintype "passive"))
      (node (ref "ACT_RfAn9") (pin "1") (pinfunction "1_1") (pintype "passive"))
      (node (ref "ACT_STM32F4DISCOVERY") (pin "21") (pinfunction "PB1/TIM3_CH4/TIM_CH3N/OTG_HS_ULPI_D2/ETH_MII_RXD3/OTG_HS_INTN/TIM1_CH3N/ADC12_IN9_21") (pintype "passive"))
    )
    (net (code "10") (name "/ACT_PB2_RFU") (class "Default")
      (node (ref "ACT_STM32F4DISCOVERY") (pin "24") (pinfunction "PB2_24") (pintype "passive"))
    )
    (net (code "11") (name "/ACT_PB4_CodDA") (class "Default")
      (node (ref "ACT_Ccod2A") (pin "2") (pinfunction "2_2") (pintype "passive"))
      (node (ref "ACT_RCod2A") (pin "1") (pinfunction "1_1") (pintype "passive"))
      (node (ref "ACT_STM32F4DISCOVERY") (pin "75") (pinfunction "PB4/NJTRST/SPI3_MISO/TIM3_CH1/SPI1_MISO/I2S3ext_SD_75") (pintype "passive"))
    )
    (net (code "12") (name "/ACT_PB5_CodDB") (class "Default")
      (node (ref "ACT_Ccod2B") (pin "2") (pinfunction "2_2") (pintype "passive"))
      (node (ref "ACT_RCod2B") (pin "1") (pinfunction "1_1") (pintype "passive"))
      (node (ref "ACT_STM32F4DISCOVERY") (pin "76") (pinfunction "PB5/I2C1_SMBA/CAN2_RX/OTG_HS_ULPI_D7/ETH_PPS_OUT/TIM3_CH2/SPI1_MOSI/SPI3_MOSI/DCMI_D10/I2S3_SD_76") (pintype "passive"))
    )
    (net (code "13") (name "/ACT_PB6_U1TX") (class "Default")
      (node (ref "ACT_RsU1tx") (pin "2") (pinfunction "2_2") (pintype "passive"))
      (node (ref "ACT_STM32F4DISCOVERY") (pin "73") (pinfunction "PB6/I2C1_SCL/TIM4_CH1/CAN2_TX/OTG_FS_INTN/DCMI_D5/USART1_TX_73") (pintype "passive"))
    )
    (net (code "14") (name "/ACT_PB7_U1RX") (class "Default")
      (node (ref "ACT_Cu1rx") (pin "2") (pinfunction "2_2") (pintype "passive"))
      (node (ref "ACT_RpuU1rx") (pin "1") (pinfunction "1_1") (pintype "passive"))
      (node (ref "ACT_Rsu1rx") (pin "1") (pinfunction "1_1") (pintype "passive"))
      (node (ref "ACT_STM32F4DISCOVERY") (pin "74") (pinfunction "PB7/I2C1_SDA/FSMC_ML/DCMI_VSYNC/USART1_RX/TIM4_CH2_74") (pintype "passive"))
    )
    (net (code "15") (name "/ACT_PB9_BallLauncher1") (class "Default")
      (node (ref "ACT_STM32F4DISCOVERY") (pin "70") (pinfunction "PB9/SPI2_NSS/I2S2_WS/TIM4_CH4/TIM11_CH1/OTG_FS_SDA/SDIO_D5/DCMI_D7/I2C1_SDA/CAN1_TX_70") (pintype "passive"))
    )
    (net (code "16") (name "/ACT_PB10_BallLauncher2") (class "Default")
      (node (ref "ACT_STM32F4DISCOVERY") (pin "34") (pinfunction "PB10/SPI2_SCK/I2S2_CK/I2C2_SCL/USART3_TX/OTG_HS_ULPI_D3/ETH_MII_RX_ER/OTG_HS_SCL/TIM2_CH3_34") (pintype "passive"))
    )
    (net (code "17") (name "/ACT_PB11_MAX485_Sens") (class "Default")
      (node (ref "ACT_MAX485") (pin "2") (pinfunction "~{RE}_2") (pintype "input"))
      (node (ref "ACT_MAX485") (pin "3") (pinfunction "DE_3") (pintype "input"))
      (node (ref "ACT_STM32F4DISCOVERY") (pin "35") (pinfunction "PB11/I2C2_SDA/USART3_RX/OTG_HS_ULPI_D4/ETH_RMII_TX_EN/ETH_MII_TX_EN/OTG_HS_SDA/TIM2_CH4_35") (pintype "passive"))
    )
    (net (code "18") (name "/ACT_PB12_BallLauncher3") (class "Default")
      (node (ref "ACT_STM32F4DISCOVERY") (pin "36") (pinfunction "PB12/SPI2_NSS/I2S2_WS/I2C2_SMBA/USART3_CK/TIM1_BKIN/CAN2_RX/OTG_HS_ULPI_D5/ETH_RMII_TXD0/ETH_MII_TXD0/OTG_HS_ID_36") (pintype "passive"))
    )
    (net (code "19") (name "/ACT_PB13_BallLauncher4") (class "Default")
      (node (ref "ACT_STM32F4DISCOVERY") (pin "37") (pinfunction "PB13/SPI2_SCK/I2S2_CK/USART3_CTS/TIM1_CH1N/CAN2_TX/OTG_HS_ULPI_D6/ETH_RMII_TXD1/ETH_MII_TXD1/OTG_HS_VBUS_37") (pintype "passive"))
    )
    (net (code "20") (name "/ACT_PB14_BallLauncher5") (class "Default")
      (node (ref "ACT_STM32F4DISCOVERY") (pin "38") (pinfunction "PB14/SPI2_MISO/TIM1_CH2N/TIM12_CH1/OTG_HS_DMUSART3_RTS/TIM8_CH2N/I2S2ext_SD_38") (pintype "passive"))
    )
    (net (code "21") (name "/ACT_PB15_BallLauncher6") (class "Default")
      (node (ref "ACT_STM32F4DISCOVERY") (pin "39") (pinfunction "PB15/SPI2_MOSI/I2S2_SD/TIM1_CH3N/TIM8_CH3N/TIM12_CH2/OTG_HS_DP_39") (pintype "passive"))
    )
    (net (code "22") (name "/ACT_PC1_ADC11") (class "Default")
      (node (ref "ACT_CfAn11") (pin "2") (pinfunction "2_2") (pintype "passive"))
      (node (ref "ACT_RfAn11") (pin "1") (pinfunction "1_1") (pintype "passive"))
      (node (ref "ACT_STM32F4DISCOVERY") (pin "7") (pinfunction "PC1/ETH_MDC/ADC123_IN11_7") (pintype "passive"))
    )
    (net (code "23") (name "/ACT_PC2_ADC12") (class "Default")
      (node (ref "ACT_CfAn12") (pin "2") (pinfunction "2_2") (pintype "passive"))
      (node (ref "ACT_RfAn12") (pin "1") (pinfunction "1_1") (pintype "passive"))
      (node (ref "ACT_STM32F4DISCOVERY") (pin "10") (pinfunction "PC2/SPI2_MISO/OTG_HS_ULPI_DIR/TH_MII_TXD2/I2S2ext_SD/ADC123_IN12_10") (pintype "passive"))
    )
    (net (code "24") (name "/ACT_PC3_ADC13") (class "Default")
      (node (ref "ACT_CfAn13") (pin "2") (pinfunction "2_2") (pintype "passive"))
      (node (ref "ACT_RfAn13") (pin "1") (pinfunction "1_1") (pintype "passive"))
      (node (ref "ACT_STM32F4DISCOVERY") (pin "9") (pinfunction "PC3/SPI2_MOSI/I2S2_SD/OTG_HS_ULPI_NXT/ETH_MII_TX_CLK/ADC123_IN13_9") (pintype "passive"))
    )
    (net (code "25") (name "/ACT_PC4_ADC14") (class "Default")
      (node (ref "ACT_CfAn14") (pin "2") (pinfunction "2_2") (pintype "passive"))
      (node (ref "ACT_RfAn14") (pin "1") (pinfunction "1_1") (pintype "passive"))
      (node (ref "ACT_STM32F4DISCOVERY") (pin "20") (pinfunction "PC4/ETH_RMII_RX_D0/ETH_MII_RX_D0/ADC12_IN14_20") (pintype "passive"))
    )
    (net (code "26") (name "/ACT_PC5_ADC15") (class "Default")
      (node (ref "ACT_CfAn15") (pin "2") (pinfunction "2_2") (pintype "passive"))
      (node (ref "ACT_RfAn15") (pin "1") (pinfunction "1_1") (pintype "passive"))
      (node (ref "ACT_STM32F4DISCOVERY") (pin "19") (pinfunction "PC5/ETH_RMII_RX_D1/ETH_MII_RX_D1/ADC12_IN15_19") (pintype "passive"))
    )
    (net (code "27") (name "/ACT_PC6_PWM1") (class "Default")
      (node (ref "ACT_STM32F4DISCOVERY") (pin "97") (pinfunction "PC6/I2S2_MCK/TIM8_CH1/SDIO_D6/USART6_TX/DCMI_D0/TIM3_CH1_97") (pintype "passive"))
      (node (ref "ACT__Mot12") (pin "2") (pinfunction "2_2") (pintype "passive"))
    )
    (net (code "28") (name "/ACT_PC7_PWM2") (class "Default")
      (node (ref "ACT_STM32F4DISCOVERY") (pin "98") (pinfunction "PC7/I2S3_MCK/TIM8_CH2/SDIO_D7/USART6_RX_DCMI_D1/TIM3_CH2_98") (pintype "passive"))
      (node (ref "ACT__Mot12") (pin "5") (pinfunction "5_5") (pintype "passive"))
    )
    (net (code "29") (name "/ACT_PC8_PWM3") (class "Default")
      (node (ref "ACT_STM32F4DISCOVERY") (pin "95") (pinfunction "PC8/TIM8_CH3/SDIO_D0/TIM3_CH3/USART6_CK/DCMI_D2_95") (pintype "passive"))
      (node (ref "ACT_mot34") (pin "2") (pinfunction "2_2") (pintype "passive"))
    )
    (net (code "30") (name "/ACT_PC9_PWM4") (class "Default")
      (node (ref "ACT_STM32F4DISCOVERY") (pin "96") (pinfunction "PC9/I2S_CKIN/MCO2/TIM8_CH4/SDIO_D1/I2C3_SDA/DCMI_D3/TIM3_CH4_96") (pintype "passive"))
      (node (ref "ACT_mot34") (pin "5") (pinfunction "5_5") (pintype "passive"))
    )
    (net (code "31") (name "/ACT_PC10_Sens2") (class "Default")
      (node (ref "ACT_STM32F4DISCOVERY") (pin "87") (pinfunction "PC10/SPI3_SCK/I2S3_CK/UART4_TX/SDIO_D2/DCMI_D8/USART3_TX_87") (pintype "passive"))
      (node (ref "ACT__Mot12") (pin "6") (pinfunction "6_6") (pintype "passive"))
    )
    (net (code "32") (name "/ACT_PC11_Sens3") (class "Default")
      (node (ref "ACT_STM32F4DISCOVERY") (pin "88") (pinfunction "PC11/UART4_RX/SPI3_MISO/SDIO_D3/DCMI_D4/USART3_RX/I2S3ext_SD_88") (pintype "passive"))
      (node (ref "ACT_mot34") (pin "1") (pinfunction "1_1") (pintype "passive"))
    )
    (net (code "33") (name "/ACT_PC12_Sens4") (class "Default")
      (node (ref "ACT_STM32F4DISCOVERY") (pin "85") (pinfunction "PC12/UART5_TX/SDIO_CK/DCMI_D9/SPI3_MOSI/I2S3_SD/USART3_CK_85") (pintype "passive"))
      (node (ref "ACT_mot34") (pin "6") (pinfunction "6_6") (pintype "passive"))
    )
    (net (code "34") (name "/ACT_PC13_WHO_AM_I") (class "Default")
      (node (ref "ACT_RdwnWAmI") (pin "2") (pinfunction "2_2") (pintype "passive"))
      (node (ref "ACT_RupWAmI") (pin "1") (pinfunction "1_1") (pintype "passive"))
      (node (ref "ACT_STM32F4DISCOVERY") (pin "62") (pinfunction "PC13/RTC_AF1_62") (pintype "passive"))
    )
    (net (code "35") (name "/ACT_PD0_CANRX") (class "Default")
      (node (ref "ACT_STM32F4DISCOVERY") (pin "86") (pinfunction "PD0/FSMC_D2/CAN1_RX_86") (pintype "passive"))
      (node (ref "ACT_Ucan") (pin "4") (pinfunction "RXD_4") (pintype "output"))
    )
    (net (code "36") (name "/ACT_PD1_CANTX") (class "Default")
      (node (ref "ACT_STM32F4DISCOVERY") (pin "83") (pinfunction "PD1/FSMC_D3/CAN1_TX_83") (pintype "passive"))
      (node (ref "ACT_Ucan") (pin "1") (pinfunction "TXD_1") (pintype "input"))
    )
    (net (code "37") (name "/ACT_PD2_TOR1") (class "Default")
      (node (ref "ACT_DrTor1") (pin "3") (pinfunction "In_3") (pintype "passive"))
      (node (ref "ACT_RpdDrTor1") (pin "2") (pinfunction "2_2") (pintype "passive"))
      (node (ref "ACT_STM32F4DISCOVERY") (pin "84") (pinfunction "PD2/TIM3_ETR/UART5_RXSDIO_CMD/DCMI_D11_84") (pintype "passive"))
    )
    (net (code "38") (name "/ACT_PD3_TOR2") (class "Default")
      (node (ref "ACT_DrTor2") (pin "3") (pinfunction "In_3") (pintype "passive"))
      (node (ref "ACT_RpdDrTor2") (pin "2") (pinfunction "2_2") (pintype "passive"))
      (node (ref "ACT_STM32F4DISCOVERY") (pin "81") (pinfunction "PD3/FSMC_CLK/USART2_CTS_81") (pintype "passive"))
    )
    (net (code "39") (name "/ACT_PD6_RFU") (class "Default")
      (node (ref "ACT_RFU") (pin "3") (pinfunction "3_3") (pintype "passive"))
      (node (ref "ACT_STM32F4DISCOVERY") (pin "80") (pinfunction "PD6/FSMC_NWAIT/USART2_RX_80") (pintype "passive"))
    )
    (net (code "40") (name "/ACT_PD7_RFU") (class "Default")
      (node (ref "ACT_RFU") (pin "2") (pinfunction "2_2") (pintype "passive"))
      (node (ref "ACT_STM32F4DISCOVERY") (pin "77") (pinfunction "PD7/USART2_CK/FSMC_NE1/FSMC_NCE2_77") (pintype "passive"))
    )
    (net (code "41") (name "/ACT_PD8_MAX485_TX") (class "Default")
      (node (ref "ACT_MAX485") (pin "4") (pinfunction "DI_4") (pintype "input"))
      (node (ref "ACT_STM32F4DISCOVERY") (pin "40") (pinfunction "PD8/FSMC_D13/USART3_TX_40") (pintype "passive"))
    )
    (net (code "42") (name "/ACT_PD9_MAX485_RX") (class "Default")
      (node (ref "ACT_MAX485") (pin "1") (pinfunction "RO_1") (pintype "tri_state"))
      (node (ref "ACT_STM32F4DISCOVERY") (pin "41") (pinfunction "PD9/FSMC_D14/USART3_RX_41") (pintype "passive"))
    )
    (net (code "43") (name "/ACT_PD10_ERROR") (class "Default")
      (node (ref "ACT_Rderror") (pin "1") (pinfunction "1_1") (pintype "passive"))
      (node (ref "ACT_STM32F4DISCOVERY") (pin "42") (pinfunction "PD10/FSMC_D15/USART3_CK_42") (pintype "passive"))
    )
    (net (code "44") (name "/ACT_PD11_SELFTEST") (class "Default")
      (node (ref "ACT_Rdselftest") (pin "1") (pinfunction "1_1") (pintype "passive"))
      (node (ref "ACT_STM32F4DISCOVERY") (pin "43") (pinfunction "PD11/FSMC_A16/USART3_CTS_43") (pintype "passive"))
    )
    (net (code "45") (name "/ACT_PD12_RUN") (class "Default")
      (node (ref "ACT_Rdrun") (pin "1") (pinfunction "1_1") (pintype "passive"))
      (node (ref "ACT_STM32F4DISCOVERY") (pin "44") (pinfunction "PD12/FSMC_A17/TIM4_CH1/USART3_RTS_44") (pintype "passive"))
    )
    (net (code "46") (name "/ACT_PD13_CAN") (class "Default")
      (node (ref "ACT_Rdcan") (pin "1") (pinfunction "1_1") (pintype "passive"))
      (node (ref "ACT_STM32F4DISCOVERY") (pin "45") (pinfunction "PD13/FSMC_A18/TIM4_CH2_45") (pintype "passive"))
    )
    (net (code "47") (name "/ACT_PD14_UART") (class "Default")
      (node (ref "ACT_Rduart") (pin "1") (pinfunction "1_1") (pintype "passive"))
      (node (ref "ACT_STM32F4DISCOVERY") (pin "46") (pinfunction "PD14/FSMC_D0/TIM4_CH3_46") (pintype "passive"))
    )
    (net (code "48") (name "/ACT_PD15_USER") (class "Default")
      (node (ref "ACT_Rduser") (pin "1") (pinfunction "1_1") (pintype "passive"))
      (node (ref "ACT_STM32F4DISCOVERY") (pin "47") (pinfunction "PD15/FSMC_D1/TIM4_CH4_47") (pintype "passive"))
    )
    (net (code "49") (name "/ACT_PE7_Divers1") (class "Default")
      (node (ref "ACT_CfswE7") (pin "2") (pinfunction "2_2") (pintype "passive"))
      (node (ref "ACT_RsSwE7") (pin "2") (pinfunction "2_2") (pintype "passive"))
      (node (ref "ACT_STM32F4DISCOVERY") (pin "25") (pinfunction "PE7/FSMC_D4/TIM1_ETR_25") (pintype "passive"))
    )
    (net (code "50") (name "/ACT_PE8_Divers2") (class "Default")
      (node (ref "ACT_CfswE8") (pin "2") (pinfunction "2_2") (pintype "passive"))
      (node (ref "ACT_RsSwE8") (pin "2") (pinfunction "2_2") (pintype "passive"))
      (node (ref "ACT_STM32F4DISCOVERY") (pin "26") (pinfunction "PE8/FSMC_D5/TIM1_CH1N_26") (pintype "passive"))
    )
    (net (code "51") (name "/ACT_PE9_Divers3") (class "Default")
      (node (ref "ACT_CfswE9") (pin "2") (pinfunction "2_2") (pintype "passive"))
      (node (ref "ACT_RsSwE9") (pin "2") (pinfunction "2_2") (pintype "passive"))
      (node (ref "ACT_STM32F4DISCOVERY") (pin "27") (pinfunction "PE9/FSMC_D6/TIM1_CH1_27") (pintype "passive"))
    )
    (net (code "52") (name "/ACT_PE10_Divers4") (class "Default")
      (node (ref "ACT_CfswE10") (pin "2") (pinfunction "2_2") (pintype "passive"))
      (node (ref "ACT_RsSwE10") (pin "2") (pinfunction "2_2") (pintype "passive"))
      (node (ref "ACT_STM32F4DISCOVERY") (pin "28") (pinfunction "PE10/FSMC_D7/TIM1_CH2N_28") (pintype "passive"))
    )
    (net (code "53") (name "/ACT_PE11_Divers5") (class "Default")
      (node (ref "ACT_CfswE11") (pin "2") (pinfunction "2_2") (pintype "passive"))
      (node (ref "ACT_RsSwE11") (pin "2") (pinfunction "2_2") (pintype "passive"))
      (node (ref "ACT_STM32F4DISCOVERY") (pin "29") (pinfunction "PE11/FSMC_D8/TIM1_CH2_29") (pintype "passive"))
    )
    (net (code "54") (name "/ACT_PE12_BP_Test_Act") (class "Default")
      (node (ref "ACT_CfBPE12") (pin "2") (pinfunction "2_2") (pintype "passive"))
      (node (ref "ACT_RsBPE12") (pin "2") (pinfunction "2_2") (pintype "passive"))
      (node (ref "ACT_STM32F4DISCOVERY") (pin "30") (pinfunction "PE12/FSMC_D9/TIM1_CH3N_30") (pintype "passive"))
    )
    (net (code "55") (name "/ACT_PE13_BP_Test_Act") (class "Default")
      (node (ref "ACT_CfBPE13") (pin "2") (pinfunction "2_2") (pintype "passive"))
      (node (ref "ACT_RsBPE13") (pin "2") (pinfunction "2_2") (pintype "passive"))
      (node (ref "ACT_STM32F4DISCOVERY") (pin "31") (pinfunction "PE13/FSMC_D10/TIM1_CH3_31") (pintype "passive"))
    )
    (net (code "56") (name "/ACT_PE14_BP_Test_Act") (class "Default")
      (node (ref "ACT_CfBPE14") (pin "2") (pinfunction "2_2") (pintype "passive"))
      (node (ref "ACT_RsBPE14") (pin "2") (pinfunction "2_2") (pintype "passive"))
      (node (ref "ACT_STM32F4DISCOVERY") (pin "32") (pinfunction "PE14/FSMC_D11/TIM1_CH4_32") (pintype "passive"))
    )
    (net (code "57") (name "/ACT_PE15_BP_Test_Act") (class "Default")
      (node (ref "ACT_CfBPE15") (pin "2") (pinfunction "2_2") (pintype "passive"))
      (node (ref "ACT_RsBPE15") (pin "2") (pinfunction "2_2") (pintype "passive"))
      (node (ref "ACT_STM32F4DISCOVERY") (pin "33") (pinfunction "PE15/FSMC_D12/TIM1_BKIN_33") (pintype "passive"))
    )
    (net (code "58") (name "/ACT_U1RX") (class "Default")
      (node (ref "ACT_Rsu1rx") (pin "2") (pinfunction "2_2") (pintype "passive"))
      (node (ref "ACT_UART1") (pin "4") (pinfunction "4_4") (pintype "passive"))
    )
    (net (code "59") (name "/ACT_U1TX") (class "Default")
      (node (ref "ACT_RpuU1tx") (pin "1") (pinfunction "1_1") (pintype "passive"))
      (node (ref "ACT_RsU1tx") (pin "1") (pinfunction "1_1") (pintype "passive"))
      (node (ref "ACT_UART1") (pin "3") (pinfunction "3_3") (pintype "passive"))
    )
    (net (code "60") (name "/CANH") (class "Default")
      (node (ref "ACT_Ucan") (pin "7") (pinfunction "CANH_7") (pintype "bidirectional"))
    )
    (net (code "61") (name "/CANL") (class "Default")
      (node (ref "ACT_Ucan") (pin "6") (pinfunction "CANL_6") (pintype "bidirectional"))
    )
    (net (code "62") (name "/MaxD") (class "Default")
      (node (ref "ACT_AX12") (pin "3") (pinfunction "3_3") (pintype "passive"))
      (node (ref "ACT_MAX485") (pin "6") (pinfunction "A_6") (pintype "bidirectional"))
      (node (ref "ACT_RpuMAX485") (pin "1") (pinfunction "1_1") (pintype "passive"))
    )
    (net (code "63") (name "/MaxD+") (class "Default")
      (node (ref "ACT_MAX485dif") (pin "6") (pinfunction "A_6") (pintype "bidirectional"))
      (node (ref "ACT_RX24") (pin "3") (pinfunction "3_3") (pintype "passive"))
      (node (ref "ACT_RpuMax485dif") (pin "1") (pinfunction "1_1") (pintype "passive"))
    )
    (net (code "64") (name "/MaxD-") (class "Default")
      (node (ref "ACT_MAX485dif") (pin "7") (pinfunction "~{B}_7") (pintype "bidirectional"))
      (node (ref "ACT_RX24") (pin "4") (pinfunction "4_4") (pintype "passive"))
    )
    (net (code "65") (name "3V_ACT") (class "Default")
      (node (ref "ACT_RpuBPE12") (pin "2") (pinfunction "2_2") (pintype "passive"))
      (node (ref "ACT_RpuBPE13") (pin "2") (pinfunction "2_2") (pintype "passive"))
      (node (ref "ACT_RpuBPE14") (pin "2") (pinfunction "2_2") (pintype "passive"))
      (node (ref "ACT_RpuBPE15") (pin "2") (pinfunction "2_2") (pintype "passive"))
      (node (ref "ACT_RpuU1rx") (pin "2") (pinfunction "2_2") (pintype "passive"))
      (node (ref "ACT_RpuU1tx") (pin "2") (pinfunction "2_2") (pintype "passive"))
      (node (ref "ACT_RpuswE10") (pin "2") (pinfunction "2_2") (pintype "passive"))
      (node (ref "ACT_RpuswE11") (pin "2") (pinfunction "2_2") (pintype "passive"))
      (node (ref "ACT_RpuswE7") (pin "2") (pinfunction "2_2") (pintype "passive"))
      (node (ref "ACT_RpuswE8") (pin "2") (pinfunction "2_2") (pintype "passive"))
      (node (ref "ACT_RpuswE9") (pin "2") (pinfunction "2_2") (pintype "passive"))
      (node (ref "ACT_RupWAmI") (pin "2") (pinfunction "2_2") (pintype "passive"))
      (node (ref "ACT_STM32F4DISCOVERY") (pin "55") (pinfunction "3V_55") (pintype "passive"))
      (node (ref "ACT_STM32F4DISCOVERY") (pin "56") (pinfunction "3V_56") (pintype "passive"))
    )
    (net (code "66") (name "5V") (class "Default")
      (node (ref "ACT_AN11") (pin "4") (pinfunction "4_4") (pintype "passive"))
      (node (ref "ACT_AN12") (pin "4") (pinfunction "4_4") (pintype "passive"))
      (node (ref "ACT_AN13") (pin "4") (pinfunction "4_4") (pintype "passive"))
      (node (ref "ACT_AN7") (pin "4") (pinfunction "4_4") (pintype "passive"))
      (node (ref "ACT_AN9") (pin "4") (pinfunction "4_4") (pintype "passive"))
      (node (ref "ACT_CdCan1") (pin "2") (pinfunction "2_2") (pintype "passive"))
      (node (ref "ACT_CdCan2") (pin "2") (pinfunction "2_2") (pintype "passive"))
      (node (ref "ACT_CdDrTor1") (pin "1") (pinfunction "1_1") (pintype "passive"))
      (node (ref "ACT_CdDrTor2") (pin "1") (pinfunction "1_1") (pintype "passive"))
      (node (ref "ACT_CdMax485") (pin "2") (pinfunction "2_2") (pintype "passive"))
      (node (ref "ACT_CdMax485dif") (pin "2") (pinfunction "2_2") (pintype "passive"))
      (node (ref "ACT_DrTor1") (pin "2") (pinfunction "Vdd_2") (pintype "passive"))
      (node (ref "ACT_DrTor2") (pin "2") (pinfunction "Vdd_2") (pintype "passive"))
      (node (ref "ACT_MAX485") (pin "8") (pinfunction "VCC_8") (pintype "passive"))
      (node (ref "ACT_MAX485dif") (pin "8") (pinfunction "VCC_8") (pintype "passive"))
      (node (ref "ACT_Rmax485B+") (pin "2") (pinfunction "2_2") (pintype "passive"))
      (node (ref "ACT_RpuMAX485") (pin "2") (pinfunction "2_2") (pintype "passive"))
      (node (ref "ACT_RpuMax485dif") (pin "2") (pinfunction "2_2") (pintype "passive"))
      (node (ref "ACT_STM32F4DISCOVERY") (pin "53") (pinfunction "5V_53") (pintype "passive"))
      (node (ref "ACT_STM32F4DISCOVERY") (pin "54") (pinfunction "5V_54") (pintype "passive"))
      (node (ref "ACT_Ucan") (pin "3") (pinfunction "VDD_3") (pintype "power_in"))
      (node (ref "ACT_cod1") (pin "1") (pinfunction "1_1") (pintype "passive"))
      (node (ref "ACT_cod1") (pin "2") (pinfunction "2_2") (pintype "passive"))
      (node (ref "ACT_cod2") (pin "1") (pinfunction "1_1") (pintype "passive"))
      (node (ref "ACT_cod2") (pin "2") (pinfunction "2_2") (pintype "passive"))
    )
    (net (code "67") (name "12V") (class "Default")
      (node (ref "ACT_AX12") (pin "2") (pinfunction "2_2") (pintype "passive"))
      (node (ref "ACT_RX24") (pin "2") (pinfunction "2_2") (pintype "passive"))
    )
    (net (code "68") (name "24V") (class "Default")
      (node (ref "ACT_AN11") (pin "3") (pinfunction "3_3") (pintype "passive"))
      (node (ref "ACT_AN12") (pin "3") (pinfunction "3_3") (pintype "passive"))
      (node (ref "ACT_AN13") (pin "3") (pinfunction "3_3") (pintype "passive"))
      (node (ref "ACT_AN7") (pin "3") (pinfunction "3_3") (pintype "passive"))
      (node (ref "ACT_AN8") (pin "3") (pinfunction "3_3") (pintype "passive"))
      (node (ref "ACT_AN9") (pin "3") (pinfunction "3_3") (pintype "passive"))
      (node (ref "ACT_CdAN11") (pin "2") (pinfunction "2_2") (pintype "passive"))
      (node (ref "ACT_CdAN12") (pin "2") (pinfunction "2_2") (pintype "passive"))
      (node (ref "ACT_CdAN13") (pin "2") (pinfunction "2_2") (pintype "passive"))
      (node (ref "ACT_CdAN7") (pin "2") (pinfunction "2_2") (pintype "passive"))
      (node (ref "ACT_CdAN8") (pin "2") (pinfunction "2_2") (pintype "passive"))
      (node (ref "ACT_CdAN9") (pin "2") (pinfunction "2_2") (pintype "passive"))
      (node (ref "ACT_tor1") (pin "1") (pinfunction "1_1") (pintype "passive"))
      (node (ref "ACT_tor2") (pin "1") (pinfunction "1_1") (pintype "passive"))
    )
    (net (code "69") (name "GND") (class "Default")
      (node (ref "ACT_BPE12") (pin "1") (pinfunction "1_1") (pintype "passive"))
      (node (ref "ACT_BPE13") (pin "1") (pinfunction "1_1") (pintype "passive"))
      (node (ref "ACT_BPE14") (pin "1") (pinfunction "1_1") (pintype "passive"))
      (node (ref "ACT_BPE15") (pin "1") (pinfunction "1_1") (pintype "passive"))
      (node (ref "ACT_Ccod1A") (pin "1") (pinfunction "1_1") (pintype "passive"))
      (node (ref "ACT_Ccod1B") (pin "1") (pinfunction "1_1") (pintype "passive"))
      (node (ref "ACT_Ccod2A") (pin "1") (pinfunction "1_1") (pintype "passive"))
      (node (ref "ACT_Ccod2B") (pin "1") (pinfunction "1_1") (pintype "passive"))
      (node (ref "ACT_CdCan1") (pin "1") (pinfunction "1_1") (pintype "passive"))
      (node (ref "ACT_CdCan2") (pin "1") (pinfunction "1_1") (pintype "passive"))
      (node (ref "ACT_CdMax485") (pin "1") (pinfunction "1_1") (pintype "passive"))
      (node (ref "ACT_CdMax485dif") (pin "1") (pinfunction "1_1") (pintype "passive"))
      (node (ref "ACT_CfAn11") (pin "1") (pinfunction "1_1") (pintype "passive"))
      (node (ref "ACT_CfAn12") (pin "1") (pinfunction "1_1") (pintype "passive"))
      (node (ref "ACT_CfAn13") (pin "1") (pinfunction "1_1") (pintype "passive"))
      (node (ref "ACT_CfAn14") (pin "1") (pinfunction "1_1") (pintype "passive"))
      (node (ref "ACT_CfAn15") (pin "1") (pinfunction "1_1") (pintype "passive"))
      (node (ref "ACT_CfAn7") (pin "1") (pinfunction "1_1") (pintype "passive"))
      (node (ref "ACT_CfAn8") (pin "1") (pinfunction "1_1") (pintype "passive"))
      (node (ref "ACT_CfAn9") (pin "1") (pinfunction "1_1") (pintype "passive"))
      (node (ref "ACT_CfBPE12") (pin "1") (pinfunction "1_1") (pintype "passive"))
      (node (ref "ACT_CfBPE13") (pin "1") (pinfunction "1_1") (pintype "passive"))
      (node (ref "ACT_CfBPE14") (pin "1") (pinfunction "1_1") (pintype "passive"))
      (node (ref "ACT_CfBPE15") (pin "1") (pinfunction "1_1") (pintype "passive"))
      (node (ref "ACT_CfswE10") (pin "1") (pinfunction "1_1") (pintype "passive"))
      (node (ref "ACT_CfswE11") (pin "1") (pinfunction "1_1") (pintype "passive"))
      (node (ref "ACT_CfswE7") (pin "1") (pinfunction "1_1") (pintype "passive"))
      (node (ref "ACT_CfswE8") (pin "1") (pinfunction "1_1") (pintype "passive"))
      (node (ref "ACT_CfswE9") (pin "1") (pinfunction "1_1") (pintype "passive"))
      (node (ref "ACT_Cu1rx") (pin "1") (pinfunction "1_1") (pintype "passive"))
      (node (ref "ACT_DSelftest") (pin "2") (pinfunction "K_2") (pintype "passive"))
      (node (ref "ACT_Dcan") (pin "2") (pinfunction "K_2") (pintype "passive"))
      (node (ref "ACT_Derror") (pin "2") (pinfunction "K_2") (pintype "passive"))
      (node (ref "ACT_Drun") (pin "2") (pinfunction "K_2") (pintype "passive"))
      (node (ref "ACT_Duart") (pin "2") (pinfunction "K_2") (pintype "passive"))
      (node (ref "ACT_Duser") (pin "2") (pinfunction "K_2") (pintype "passive"))
      (node (ref "ACT_MAX485") (pin "5") (pinfunction "GND_5") (pintype "passive"))
      (node (ref "ACT_MAX485dif") (pin "5") (pinfunction "GND_5") (pintype "passive"))
      (node (ref "ACT_RFU") (pin "1") (pinfunction "1_1") (pintype "passive"))
      (node (ref "ACT_RdwnAn11") (pin "1") (pinfunction "1_1") (pintype "passive"))
      (node (ref "ACT_RdwnAn12") (pin "1") (pinfunction "1_1") (pintype "passive"))
      (node (ref "ACT_RdwnAn13") (pin "1") (pinfunction "1_1") (pintype "passive"))
      (node (ref "ACT_RdwnAn7") (pin "1") (pinfunction "1_1") (pintype "passive"))
      (node (ref "ACT_RdwnAn8") (pin "1") (pinfunction "1_1") (pintype "passive"))
      (node (ref "ACT_RdwnAn9") (pin "1") (pinfunction "1_1") (pintype "passive"))
      (node (ref "ACT_RdwnWAmI") (pin "1") (pinfunction "1_1") (pintype "passive"))
      (node (ref "ACT_Rmax485B-") (pin "1") (pinfunction "1_1") (pintype "passive"))
      (node (ref "ACT_RpdDrTor1") (pin "1") (pinfunction "1_1") (pintype "passive"))
      (node (ref "ACT_RpdDrTor2") (pin "1") (pinfunction "1_1") (pintype "passive"))
      (node (ref "ACT_STM32F4DISCOVERY") (pin "1") (pinfunction "GND_1") (pintype "passive"))
      (node (ref "ACT_STM32F4DISCOVERY") (pin "100") (pinfunction "GND_100") (pintype "passive"))
      (node (ref "ACT_STM32F4DISCOVERY") (pin "2") (pinfunction "GND_2") (pintype "passive"))
      (node (ref "ACT_STM32F4DISCOVERY") (pin "23") (pinfunction "GND_23") (pintype "passive"))
      (node (ref "ACT_STM32F4DISCOVERY") (pin "49") (pinfunction "GND_49") (pintype "passive"))
      (node (ref "ACT_STM32F4DISCOVERY") (pin "5") (pinfunction "GND_5") (pintype "passive"))
      (node (ref "ACT_STM32F4DISCOVERY") (pin "50") (pinfunction "GND_50") (pintype "passive"))
      (node (ref "ACT_STM32F4DISCOVERY") (pin "51") (pinfunction "GND_51") (pintype "passive"))
      (node (ref "ACT_STM32F4DISCOVERY") (pin "52") (pinfunction "GND_52") (pintype "passive"))
      (node (ref "ACT_STM32F4DISCOVERY") (pin "99") (pinfunction "GND_99") (pintype "passive"))
      (node (ref "ACT_SwE10") (pin "COMMON1") (pinfunction "COMMON1_COMMON1") (pintype "passive"))
      (node (ref "ACT_SwE11") (pin "COMMON1") (pinfunction "COMMON1_COMMON1") (pintype "passive"))
      (node (ref "ACT_SwE7") (pin "COMMON1") (pinfunction "COMMON1_COMMON1") (pintype "passive"))
      (node (ref "ACT_SwE8") (pin "COMMON1") (pinfunction "COMMON1_COMMON1") (pintype "passive"))
      (node (ref "ACT_SwE9") (pin "COMMON1") (pinfunction "COMMON1_COMMON1") (pintype "passive"))
      (node (ref "ACT_UART1") (pin "5") (pinfunction "5_5") (pintype "passive"))
      (node (ref "ACT_UART1") (pin "6") (pinfunction "6_6") (pintype "passive"))
      (node (ref "ACT_Ucan") (pin "2") (pinfunction "VSS_2") (pintype "power_in"))
      (node (ref "ACT_Ucan") (pin "8") (pinfunction "RS_8") (pintype "input"))
      (node (ref "ACT__Mot12") (pin "3") (pinfunction "3_3") (pintype "passive"))
      (node (ref "ACT__Mot12") (pin "4") (pinfunction "4_4") (pintype "passive"))
      (node (ref "ACT_cod1") (pin "5") (pinfunction "5_5") (pintype "passive"))
      (node (ref "ACT_cod1") (pin "6") (pinfunction "6_6") (pintype "passive"))
      (node (ref "ACT_cod2") (pin "5") (pinfunction "5_5") (pintype "passive"))
      (node (ref "ACT_cod2") (pin "6") (pinfunction "6_6") (pintype "passive"))
      (node (ref "ACT_currentMot") (pin "1") (pinfunction "1_1") (pintype "passive"))
      (node (ref "ACT_mot34") (pin "3") (pinfunction "3_3") (pintype "passive"))
      (node (ref "ACT_mot34") (pin "4") (pinfunction "4_4") (pintype "passive"))
      (node (ref "ACT_stAN11") (pin "3") (pinfunction "3_3") (pintype "passive"))
      (node (ref "ACT_stAN12") (pin "3") (pinfunction "3_3") (pintype "passive"))
      (node (ref "ACT_stAN13") (pin "3") (pinfunction "3_3") (pintype "passive"))
      (node (ref "ACT_stAN7") (pin "3") (pinfunction "3_3") (pintype "passive"))
      (node (ref "ACT_stAN9") (pin "3") (pinfunction "3_3") (pintype "passive"))
    )
    (net (code "70") (name "GND_12") (class "Default")
      (node (ref "ACT_AX12") (pin "1") (pinfunction "1_1") (pintype "passive"))
      (node (ref "ACT_RX24") (pin "1") (pinfunction "1_1") (pintype "passive"))
    )
    (net (code "71") (name "GND_24") (class "Default")
      (node (ref "ACT_AN8") (pin "1") (pinfunction "1_1") (pintype "passive"))
      (node (ref "ACT_CdAN11") (pin "1") (pinfunction "1_1") (pintype "passive"))
      (node (ref "ACT_CdAN12") (pin "1") (pinfunction "1_1") (pintype "passive"))
      (node (ref "ACT_CdAN13") (pin "1") (pinfunction "1_1") (pintype "passive"))
      (node (ref "ACT_CdAN7") (pin "1") (pinfunction "1_1") (pintype "passive"))
      (node (ref "ACT_CdAN8") (pin "1") (pinfunction "1_1") (pintype "passive"))
      (node (ref "ACT_CdAN9") (pin "1") (pinfunction "1_1") (pintype "passive"))
      (node (ref "ACT_CdDrTor1") (pin "2") (pinfunction "2_2") (pintype "passive"))
      (node (ref "ACT_CdDrTor2") (pin "2") (pinfunction "2_2") (pintype "passive"))
      (node (ref "ACT_DrTor1") (pin "1") (pinfunction "GND_1") (pintype "passive"))
      (node (ref "ACT_DrTor1") (pin "4") (pinfunction "GND_4") (pintype "passive"))
      (node (ref "ACT_DrTor2") (pin "1") (pinfunction "GND_1") (pintype "passive"))
      (node (ref "ACT_DrTor2") (pin "4") (pinfunction "GND_4") (pintype "passive"))
      (node (ref "ACT_Qtor1") (pin "3") (pinfunction "S_3") (pintype "passive"))
      (node (ref "ACT_Qtor2") (pin "3") (pinfunction "S_3") (pintype "passive"))
      (node (ref "ACT_stAN11") (pin "1") (pinfunction "1_1") (pintype "passive"))
      (node (ref "ACT_stAN12") (pin "1") (pinfunction "1_1") (pintype "passive"))
      (node (ref "ACT_stAN13") (pin "1") (pinfunction "1_1") (pintype "passive"))
      (node (ref "ACT_stAN7") (pin "1") (pinfunction "1_1") (pintype "passive"))
      (node (ref "ACT_stAN9") (pin "1") (pinfunction "1_1") (pintype "passive"))
      (node (ref "ACT_tor1") (pin "2") (pinfunction "2_2") (pintype "passive"))
      (node (ref "ACT_tor2") (pin "2") (pinfunction "2_2") (pintype "passive"))
    )
    (net (code "72") (name "Net-(ACT_AN7-Pad1)") (class "Default")
      (node (ref "ACT_AN7") (pin "1") (pinfunction "1_1") (pintype "passive"))
      (node (ref "ACT_stAN7") (pin "2") (pinfunction "2_2") (pintype "passive"))
    )
    (net (code "73") (name "Net-(ACT_AN7-Pad2)") (class "Default")
      (node (ref "ACT_AN7") (pin "2") (pinfunction "2_2") (pintype "passive"))
      (node (ref "ACT_RdwnAn7") (pin "2") (pinfunction "2_2") (pintype "passive"))
      (node (ref "ACT_RfAn7") (pin "2") (pinfunction "2_2") (pintype "passive"))
    )
    (net (code "74") (name "Net-(ACT_AN8-Pad2)") (class "Default")
      (node (ref "ACT_AN8") (pin "2") (pinfunction "2_2") (pintype "passive"))
      (node (ref "ACT_RdwnAn8") (pin "2") (pinfunction "2_2") (pintype "passive"))
      (node (ref "ACT_RfAn8") (pin "2") (pinfunction "2_2") (pintype "passive"))
    )
    (net (code "75") (name "Net-(ACT_AN9-Pad1)") (class "Default")
      (node (ref "ACT_AN9") (pin "1") (pinfunction "1_1") (pintype "passive"))
      (node (ref "ACT_stAN9") (pin "2") (pinfunction "2_2") (pintype "passive"))
    )
    (net (code "76") (name "Net-(ACT_AN9-Pad2)") (class "Default")
      (node (ref "ACT_AN9") (pin "2") (pinfunction "2_2") (pintype "passive"))
      (node (ref "ACT_RdwnAn9") (pin "2") (pinfunction "2_2") (pintype "passive"))
      (node (ref "ACT_RfAn9") (pin "2") (pinfunction "2_2") (pintype "passive"))
    )
    (net (code "77") (name "Net-(ACT_AN11-Pad1)") (class "Default")
      (node (ref "ACT_AN11") (pin "1") (pinfunction "1_1") (pintype "passive"))
      (node (ref "ACT_stAN11") (pin "2") (pinfunction "2_2") (pintype "passive"))
    )
    (net (code "78") (name "Net-(ACT_AN11-Pad2)") (class "Default")
      (node (ref "ACT_AN11") (pin "2") (pinfunction "2_2") (pintype "passive"))
      (node (ref "ACT_RdwnAn11") (pin "2") (pinfunction "2_2") (pintype "passive"))
      (node (ref "ACT_RfAn11") (pin "2") (pinfunction "2_2") (pintype "passive"))
    )
    (net (code "79") (name "Net-(ACT_AN12-Pad1)") (class "Default")
      (node (ref "ACT_AN12") (pin "1") (pinfunction "1_1") (pintype "passive"))
      (node (ref "ACT_stAN12") (pin "2") (pinfunction "2_2") (pintype "passive"))
    )
    (net (code "80") (name "Net-(ACT_AN12-Pad2)") (class "Default")
      (node (ref "ACT_AN12") (pin "2") (pinfunction "2_2") (pintype "passive"))
      (node (ref "ACT_RdwnAn12") (pin "2") (pinfunction "2_2") (pintype "passive"))
      (node (ref "ACT_RfAn12") (pin "2") (pinfunction "2_2") (pintype "passive"))
    )
    (net (code "81") (name "Net-(ACT_AN13-Pad1)") (class "Default")
      (node (ref "ACT_AN13") (pin "1") (pinfunction "1_1") (pintype "passive"))
      (node (ref "ACT_stAN13") (pin "2") (pinfunction "2_2") (pintype "passive"))
    )
    (net (code "82") (name "Net-(ACT_AN13-Pad2)") (class "Default")
      (node (ref "ACT_AN13") (pin "2") (pinfunction "2_2") (pintype "passive"))
      (node (ref "ACT_RdwnAn13") (pin "2") (pinfunction "2_2") (pintype "passive"))
      (node (ref "ACT_RfAn13") (pin "2") (pinfunction "2_2") (pintype "passive"))
    )
    (net (code "83") (name "Net-(ACT_BPE12-Pad3)") (class "Default")
      (node (ref "ACT_BPE12") (pin "3") (pinfunction "3_3") (pintype "passive"))
      (node (ref "ACT_RpuBPE12") (pin "1") (pinfunction "1_1") (pintype "passive"))
      (node (ref "ACT_RsBPE12") (pin "1") (pinfunction "1_1") (pintype "passive"))
    )
    (net (code "84") (name "Net-(ACT_BPE13-Pad3)") (class "Default")
      (node (ref "ACT_BPE13") (pin "3") (pinfunction "3_3") (pintype "passive"))
      (node (ref "ACT_RpuBPE13") (pin "1") (pinfunction "1_1") (pintype "passive"))
      (node (ref "ACT_RsBPE13") (pin "1") (pinfunction "1_1") (pintype "passive"))
    )
    (net (code "85") (name "Net-(ACT_BPE14-Pad3)") (class "Default")
      (node (ref "ACT_BPE14") (pin "3") (pinfunction "3_3") (pintype "passive"))
      (node (ref "ACT_RpuBPE14") (pin "1") (pinfunction "1_1") (pintype "passive"))
      (node (ref "ACT_RsBPE14") (pin "1") (pinfunction "1_1") (pintype "passive"))
    )
    (net (code "86") (name "Net-(ACT_BPE15-Pad3)") (class "Default")
      (node (ref "ACT_BPE15") (pin "3") (pinfunction "3_3") (pintype "passive"))
      (node (ref "ACT_RpuBPE15") (pin "1") (pinfunction "1_1") (pintype "passive"))
      (node (ref "ACT_RsBPE15") (pin "1") (pinfunction "1_1") (pintype "passive"))
    )
    (net (code "87") (name "Net-(ACT_DSelftest-A)") (class "Default")
      (node (ref "ACT_DSelftest") (pin "1") (pinfunction "A_1") (pintype "passive"))
      (node (ref "ACT_Rdselftest") (pin "2") (pinfunction "2_2") (pintype "passive"))
    )
    (net (code "88") (name "Net-(ACT_Dcan-A)") (class "Default")
      (node (ref "ACT_Dcan") (pin "1") (pinfunction "A_1") (pintype "passive"))
      (node (ref "ACT_Rdcan") (pin "2") (pinfunction "2_2") (pintype "passive"))
    )
    (net (code "89") (name "Net-(ACT_Derror-A)") (class "Default")
      (node (ref "ACT_Derror") (pin "1") (pinfunction "A_1") (pintype "passive"))
      (node (ref "ACT_Rderror") (pin "2") (pinfunction "2_2") (pintype "passive"))
    )
    (net (code "90") (name "Net-(ACT_DrTor1-OUT)") (class "Default")
      (node (ref "ACT_DrTor1") (pin "5") (pinfunction "OUT_5") (pintype "passive"))
      (node (ref "ACT_Qtor1") (pin "1") (pinfunction "G_1") (pintype "passive"))
    )
    (net (code "91") (name "Net-(ACT_DrTor2-OUT)") (class "Default")
      (node (ref "ACT_DrTor2") (pin "5") (pinfunction "OUT_5") (pintype "passive"))
      (node (ref "ACT_Qtor2") (pin "1") (pinfunction "G_1") (pintype "passive"))
    )
    (net (code "92") (name "Net-(ACT_Drun-A)") (class "Default")
      (node (ref "ACT_Drun") (pin "1") (pinfunction "A_1") (pintype "passive"))
      (node (ref "ACT_Rdrun") (pin "2") (pinfunction "2_2") (pintype "passive"))
    )
    (net (code "93") (name "Net-(ACT_Duart-A)") (class "Default")
      (node (ref "ACT_Duart") (pin "1") (pinfunction "A_1") (pintype "passive"))
      (node (ref "ACT_Rduart") (pin "2") (pinfunction "2_2") (pintype "passive"))
    )
    (net (code "94") (name "Net-(ACT_Duser-A)") (class "Default")
      (node (ref "ACT_Duser") (pin "1") (pinfunction "A_1") (pintype "passive"))
      (node (ref "ACT_Rduser") (pin "2") (pinfunction "2_2") (pintype "passive"))
    )
    (net (code "95") (name "Net-(ACT_MAX485-~{B})") (class "Default")
      (node (ref "ACT_MAX485") (pin "7") (pinfunction "~{B}_7") (pintype "bidirectional"))
      (node (ref "ACT_Rmax485B+") (pin "1") (pinfunction "1_1") (pintype "passive"))
      (node (ref "ACT_Rmax485B-") (pin "2") (pinfunction "2_2") (pintype "passive"))
    )
    (net (code "96") (name "Net-(ACT_Qtor1-D)") (class "Default")
      (node (ref "ACT_Qtor1") (pin "2") (pinfunction "D_2") (pintype "passive"))
      (node (ref "ACT_tor1") (pin "3") (pinfunction "3_3") (pintype "passive"))
    )
    (net (code "97") (name "Net-(ACT_Qtor2-D)") (class "Default")
      (node (ref "ACT_Qtor2") (pin "2") (pinfunction "D_2") (pintype "passive"))
      (node (ref "ACT_tor2") (pin "3") (pinfunction "3_3") (pintype "passive"))
    )
    (net (code "98") (name "Net-(ACT_RCod1A-Pad2)") (class "Default")
      (node (ref "ACT_RCod1A") (pin "2") (pinfunction "2_2") (pintype "passive"))
      (node (ref "ACT_cod1") (pin "3") (pinfunction "3_3") (pintype "passive"))
    )
    (net (code "99") (name "Net-(ACT_RCod1B-Pad2)") (class "Default")
      (node (ref "ACT_RCod1B") (pin "2") (pinfunction "2_2") (pintype "passive"))
      (node (ref "ACT_cod1") (pin "4") (pinfunction "4_4") (pintype "passive"))
    )
    (net (code "100") (name "Net-(ACT_RCod2A-Pad2)") (class "Default")
      (node (ref "ACT_RCod2A") (pin "2") (pinfunction "2_2") (pintype "passive"))
      (node (ref "ACT_cod2") (pin "3") (pinfunction "3_3") (pintype "passive"))
    )
    (net (code "101") (name "Net-(ACT_RCod2B-Pad2)") (class "Default")
      (node (ref "ACT_RCod2B") (pin "2") (pinfunction "2_2") (pintype "passive"))
      (node (ref "ACT_cod2") (pin "4") (pinfunction "4_4") (pintype "passive"))
    )
    (net (code "102") (name "Net-(ACT_RfAn14-Pad2)") (class "Default")
      (node (ref "ACT_RfAn14") (pin "2") (pinfunction "2_2") (pintype "passive"))
      (node (ref "ACT_currentMot") (pin "3") (pinfunction "3_3") (pintype "passive"))
    )
    (net (code "103") (name "Net-(ACT_RfAn15-Pad2)") (class "Default")
      (node (ref "ACT_RfAn15") (pin "2") (pinfunction "2_2") (pintype "passive"))
      (node (ref "ACT_currentMot") (pin "2") (pinfunction "2_2") (pintype "passive"))
    )
    (net (code "104") (name "Net-(ACT_RpuswE7-Pad1)") (class "Default")
      (node (ref "ACT_RpuswE7") (pin "1") (pinfunction "1_1") (pintype "passive"))
      (node (ref "ACT_RsSwE7") (pin "1") (pinfunction "1_1") (pintype "passive"))
      (node (ref "ACT_SwE7") (pin "NO1") (pinfunction "NO1_NO1") (pintype "passive"))
    )
    (net (code "105") (name "Net-(ACT_RpuswE8-Pad1)") (class "Default")
      (node (ref "ACT_RpuswE8") (pin "1") (pinfunction "1_1") (pintype "passive"))
      (node (ref "ACT_RsSwE8") (pin "1") (pinfunction "1_1") (pintype "passive"))
      (node (ref "ACT_SwE8") (pin "NO1") (pinfunction "NO1_NO1") (pintype "passive"))
    )
    (net (code "106") (name "Net-(ACT_RpuswE9-Pad1)") (class "Default")
      (node (ref "ACT_RpuswE9") (pin "1") (pinfunction "1_1") (pintype "passive"))
      (node (ref "ACT_RsSwE9") (pin "1") (pinfunction "1_1") (pintype "passive"))
      (node (ref "ACT_SwE9") (pin "NO1") (pinfunction "NO1_NO1") (pintype "passive"))
    )
    (net (code "107") (name "Net-(ACT_RpuswE10-Pad1)") (class "Default")
      (node (ref "ACT_RpuswE10") (pin "1") (pinfunction "1_1") (pintype "passive"))
      (node (ref "ACT_RsSwE10") (pin "1") (pinfunction "1_1") (pintype "passive"))
      (node (ref "ACT_SwE10") (pin "NO1") (pinfunction "NO1_NO1") (pintype "passive"))
    )
    (net (code "108") (name "Net-(ACT_RpuswE11-Pad1)") (class "Default")
      (node (ref "ACT_RpuswE11") (pin "1") (pinfunction "1_1") (pintype "passive"))
      (node (ref "ACT_RsSwE11") (pin "1") (pinfunction "1_1") (pintype "passive"))
      (node (ref "ACT_SwE11") (pin "NO1") (pinfunction "NO1_NO1") (pintype "passive"))
    )
    (net (code "109") (name "unconnected-(ACT_RFU-Pad4)") (class "Default")
      (node (ref "ACT_RFU") (pin "4") (pinfunction "4_4") (pintype "passive"))
    )
    (net (code "110") (name "unconnected-(ACT_STM32F4DISCOVERY-BOOT0{slash}VPP-Pad71)") (class "Default")
      (node (ref "ACT_STM32F4DISCOVERY") (pin "71") (pinfunction "BOOT0/VPP_71") (pintype "passive+no_connect"))
    )
    (net (code "111") (name "unconnected-(ACT_STM32F4DISCOVERY-NC-Pad48)") (class "Default")
      (node (ref "ACT_STM32F4DISCOVERY") (pin "48") (pinfunction "NC_48") (pintype "passive+no_connect"))
    )
    (net (code "112") (name "unconnected-(ACT_STM32F4DISCOVERY-NRST-Pad6)") (class "Default")
      (node (ref "ACT_STM32F4DISCOVERY") (pin "6") (pinfunction "NRST_6") (pintype "passive+no_connect"))
    )
    (net (code "113") (name "unconnected-(ACT_STM32F4DISCOVERY-PA0-WKUP{slash}USART2_CTS{slash}USART4_TX{slash}ETH_MII_CRS{slash}TIM2_CH1_ETR{slash}TIM5_CH1{slash}TIM8_ETR{slash}ADC123_IN0{slash}WKUP-Pad12)") (class "Default")
      (node (ref "ACT_STM32F4DISCOVERY") (pin "12") (pinfunction "PA0-WKUP/USART2_CTS/USART4_TX/ETH_MII_CRS/TIM2_CH1_ETR/TIM5_CH1/TIM8_ETR/ADC123_IN0/WKUP_12") (pintype "passive+no_connect"))
    )
    (net (code "114") (name "unconnected-(ACT_STM32F4DISCOVERY-PA4{slash}SPI1_NSS{slash}SPI3_NSS{slash}USART2_CK{slash}DCMI_HSYNC{slash}OTG_HS_SOF{slash}I2S3_WS{slash}ADC12_IN4{slash}DAC1_OUT-Pad16)") (class "Default")
      (node (ref "ACT_STM32F4DISCOVERY") (pin "16") (pinfunction "PA4/SPI1_NSS/SPI3_NSS/USART2_CK/DCMI_HSYNC/OTG_HS_SOF/I2S3_WS/ADC12_IN4/DAC1_OUT_16") (pintype "passive+no_connect"))
    )
    (net (code "115") (name "unconnected-(ACT_STM32F4DISCOVERY-PA6{slash}SPI1_MISO{slash}TIM8_BKIN{slash}TIM13_CH1{slash}DCMI_PIXCLK{slash}TIM3_CH1{slash}TIM1_BKIN{slash}ADC12_IN6-Pad18)") (class "Default")
      (node (ref "ACT_STM32F4DISCOVERY") (pin "18") (pinfunction "PA6/SPI1_MISO/TIM8_BKIN/TIM13_CH1/DCMI_PIXCLK/TIM3_CH1/TIM1_BKIN/ADC12_IN6_18") (pintype "passive+no_connect"))
    )
    (net (code "116") (name "unconnected-(ACT_STM32F4DISCOVERY-PA9{slash}USART1_TX{slash}TIM1_CH2{slash}I2C3_SMBA{slash}DCMI_D0{slash}OTG_FS_VBUS-Pad94)") (class "Default")
      (node (ref "ACT_STM32F4DISCOVERY") (pin "94") (pinfunction "PA9/USART1_TX/TIM1_CH2/I2C3_SMBA/DCMI_D0/OTG_FS_VBUS_94") (pintype "passive+no_connect"))
    )
    (net (code "117") (name "unconnected-(ACT_STM32F4DISCOVERY-PA10{slash}USART1_RX{slash}TIM1_CH3{slash}OTG_FS_ID{slash}DCMI_D1-Pad91)") (class "Default")
      (node (ref "ACT_STM32F4DISCOVERY") (pin "91") (pinfunction "PA10/USART1_RX/TIM1_CH3/OTG_FS_ID/DCMI_D1_91") (pintype "passive+no_connect"))
    )
    (net (code "118") (name "unconnected-(ACT_STM32F4DISCOVERY-PA13{slash}JTMS_SWDIO-Pad92)") (class "Default")
      (node (ref "ACT_STM32F4DISCOVERY") (pin "92") (pinfunction "PA13/JTMS_SWDIO_92") (pintype "passive+no_connect"))
    )
    (net (code "119") (name "unconnected-(ACT_STM32F4DISCOVERY-PA14{slash}JTCK_SWCLK-Pad89)") (class "Default")
      (node (ref "ACT_STM32F4DISCOVERY") (pin "89") (pinfunction "PA14/JTCK_SWCLK_89") (pintype "passive+no_connect"))
    )
    (net (code "120") (name "unconnected-(ACT_STM32F4DISCOVERY-PB3{slash}JTDO{slash}TRACESWO{slash}SPI3_SCK{slash}I2S3_CK{slash}TIM2_CH2{slash}SPI1_SCK-Pad78)") (class "Default")
      (node (ref "ACT_STM32F4DISCOVERY") (pin "78") (pinfunction "PB3/JTDO/TRACESWO/SPI3_SCK/I2S3_CK/TIM2_CH2/SPI1_SCK_78") (pintype "passive+no_connect"))
    )
    (net (code "121") (name "unconnected-(ACT_STM32F4DISCOVERY-PB8{slash}TIM4_CH3{slash}SDIO_D4{slash}TIM10_CH1{slash}DCMI_D6{slash}OTG_FS_SCL{slash}ETH_MII_TXD3{slash}I2C1_SCL{slash}CAN1_RX-Pad69)") (class "Default")
      (node (ref "ACT_STM32F4DISCOVERY") (pin "69") (pinfunction "PB8/TIM4_CH3/SDIO_D4/TIM10_CH1/DCMI_D6/OTG_FS_SCL/ETH_MII_TXD3/I2C1_SCL/CAN1_RX_69") (pintype "passive+no_connect"))
    )
    (net (code "122") (name "unconnected-(ACT_STM32F4DISCOVERY-PC0{slash}OTG_HS_ULPI_STP{slash}ADC123_IN10-Pad8)") (class "Default")
      (node (ref "ACT_STM32F4DISCOVERY") (pin "8") (pinfunction "PC0/OTG_HS_ULPI_STP/ADC123_IN10_8") (pintype "passive+no_connect"))
    )
    (net (code "123") (name "unconnected-(ACT_STM32F4DISCOVERY-PC14{slash}OSC32_IN-Pad59)") (class "Default")
      (node (ref "ACT_STM32F4DISCOVERY") (pin "59") (pinfunction "PC14/OSC32_IN_59") (pintype "passive+no_connect"))
    )
    (net (code "124") (name "unconnected-(ACT_STM32F4DISCOVERY-PC15{slash}OSC32_OUT-Pad60)") (class "Default")
      (node (ref "ACT_STM32F4DISCOVERY") (pin "60") (pinfunction "PC15/OSC32_OUT_60") (pintype "passive+no_connect"))
    )
    (net (code "125") (name "unconnected-(ACT_STM32F4DISCOVERY-PD4{slash}FSMC_NOE{slash}USART2_RTS-Pad82)") (class "Default")
      (node (ref "ACT_STM32F4DISCOVERY") (pin "82") (pinfunction "PD4/FSMC_NOE/USART2_RTS_82") (pintype "passive+no_connect"))
    )
    (net (code "126") (name "unconnected-(ACT_STM32F4DISCOVERY-PD5{slash}FSMC_NWE{slash}USART2_TX-Pad79)") (class "Default")
      (node (ref "ACT_STM32F4DISCOVERY") (pin "79") (pinfunction "PD5/FSMC_NWE/USART2_TX_79") (pintype "passive+no_connect"))
    )
    (net (code "127") (name "unconnected-(ACT_STM32F4DISCOVERY-PE0{slash}TIM4_ETR{slash}FSMC_NBL0{slash}DCMI_D2-Pad67)") (class "Default")
      (node (ref "ACT_STM32F4DISCOVERY") (pin "67") (pinfunction "PE0/TIM4_ETR/FSMC_NBL0/DCMI_D2_67") (pintype "passive+no_connect"))
    )
    (net (code "128") (name "unconnected-(ACT_STM32F4DISCOVERY-PE1{slash}FSMC_NBL1{slash}DCMI_D3-Pad68)") (class "Default")
      (node (ref "ACT_STM32F4DISCOVERY") (pin "68") (pinfunction "PE1/FSMC_NBL1/DCMI_D3_68") (pintype "passive+no_connect"))
    )
    (net (code "129") (name "unconnected-(ACT_STM32F4DISCOVERY-PE2{slash}TRACECLK{slash}FSMC_A23{slash}ETH_MII_TXD3-Pad65)") (class "Default")
      (node (ref "ACT_STM32F4DISCOVERY") (pin "65") (pinfunction "PE2/TRACECLK/FSMC_A23/ETH_MII_TXD3_65") (pintype "passive+no_connect"))
    )
    (net (code "130") (name "unconnected-(ACT_STM32F4DISCOVERY-PE3{slash}TRACED0{slash}FSMC_A19-Pad66)") (class "Default")
      (node (ref "ACT_STM32F4DISCOVERY") (pin "66") (pinfunction "PE3/TRACED0/FSMC_A19_66") (pintype "passive+no_connect"))
    )
    (net (code "131") (name "unconnected-(ACT_STM32F4DISCOVERY-PE4{slash}TRACED1{slash}FSMC_A20{slash}DCMI_D4-Pad63)") (class "Default")
      (node (ref "ACT_STM32F4DISCOVERY") (pin "63") (pinfunction "PE4/TRACED1/FSMC_A20/DCMI_D4_63") (pintype "passive+no_connect"))
    )
    (net (code "132") (name "unconnected-(ACT_STM32F4DISCOVERY-PE5{slash}TRACED2{slash}FSMC_A21{slash}TIM9_CH1{slash}DCMI_D6-Pad64)") (class "Default")
      (node (ref "ACT_STM32F4DISCOVERY") (pin "64") (pinfunction "PE5/TRACED2/FSMC_A21/TIM9_CH1/DCMI_D6_64") (pintype "passive+no_connect"))
    )
    (net (code "133") (name "unconnected-(ACT_STM32F4DISCOVERY-PE6{slash}TRACED3{slash}FSMC_A22{slash}TIM9_CH2{slash}DCMI_D7-Pad61)") (class "Default")
      (node (ref "ACT_STM32F4DISCOVERY") (pin "61") (pinfunction "PE6/TRACED3/FSMC_A22/TIM9_CH2/DCMI_D7_61") (pintype "passive+no_connect"))
    )
    (net (code "134") (name "unconnected-(ACT_STM32F4DISCOVERY-PH0{slash}OSC_IN-Pad57)") (class "Default")
      (node (ref "ACT_STM32F4DISCOVERY") (pin "57") (pinfunction "PH0/OSC_IN_57") (pintype "passive+no_connect"))
    )
    (net (code "135") (name "unconnected-(ACT_STM32F4DISCOVERY-PH1{slash}OSC_OUT-Pad58)") (class "Default")
      (node (ref "ACT_STM32F4DISCOVERY") (pin "58") (pinfunction "PH1/OSC_OUT_58") (pintype "passive+no_connect"))
    )
    (net (code "136") (name "unconnected-(ACT_STM32F4DISCOVERY-VDD-Pad3)") (class "Default")
      (node (ref "ACT_STM32F4DISCOVERY") (pin "3") (pinfunction "VDD_3") (pintype "passive+no_connect"))
    )
    (net (code "137") (name "unconnected-(ACT_STM32F4DISCOVERY-VDD-Pad4)") (class "Default")
      (node (ref "ACT_STM32F4DISCOVERY") (pin "4") (pinfunction "VDD_4") (pintype "passive+no_connect"))
    )
    (net (code "138") (name "unconnected-(ACT_STM32F4DISCOVERY-VDD-Pad72)") (class "Default")
      (node (ref "ACT_STM32F4DISCOVERY") (pin "72") (pinfunction "VDD_72") (pintype "passive+no_connect"))
    )
    (net (code "139") (name "unconnected-(ACT_SwE7-PadNC1)") (class "Default")
      (node (ref "ACT_SwE7") (pin "NC1") (pinfunction "NC1_NC1") (pintype "passive+no_connect"))
    )
    (net (code "140") (name "unconnected-(ACT_SwE8-PadNC1)") (class "Default")
      (node (ref "ACT_SwE8") (pin "NC1") (pinfunction "NC1_NC1") (pintype "passive+no_connect"))
    )
    (net (code "141") (name "unconnected-(ACT_SwE9-PadNC1)") (class "Default")
      (node (ref "ACT_SwE9") (pin "NC1") (pinfunction "NC1_NC1") (pintype "passive+no_connect"))
    )
    (net (code "142") (name "unconnected-(ACT_SwE10-PadNC1)") (class "Default")
      (node (ref "ACT_SwE10") (pin "NC1") (pinfunction "NC1_NC1") (pintype "passive+no_connect"))
    )
    (net (code "143") (name "unconnected-(ACT_SwE11-PadNC1)") (class "Default")
      (node (ref "ACT_SwE11") (pin "NC1") (pinfunction "NC1_NC1") (pintype "passive+no_connect"))
    )
    (net (code "144") (name "unconnected-(ACT_UART1-Pad1)") (class "Default")
      (node (ref "ACT_UART1") (pin "1") (pinfunction "1_1") (pintype "passive+no_connect"))
    )
    (net (code "145") (name "unconnected-(ACT_UART1-Pad2)") (class "Default")
      (node (ref "ACT_UART1") (pin "2") (pinfunction "2_2") (pintype "passive+no_connect"))
    )
    (net (code "146") (name "unconnected-(ACT_Ucan-VREF-Pad5)") (class "Default")
      (node (ref "ACT_Ucan") (pin "5") (pinfunction "VREF_5") (pintype "output"))
    )
  )
)
